# rev_n_v32.net
KiCad netlist of a schematic drawn in EAGLE
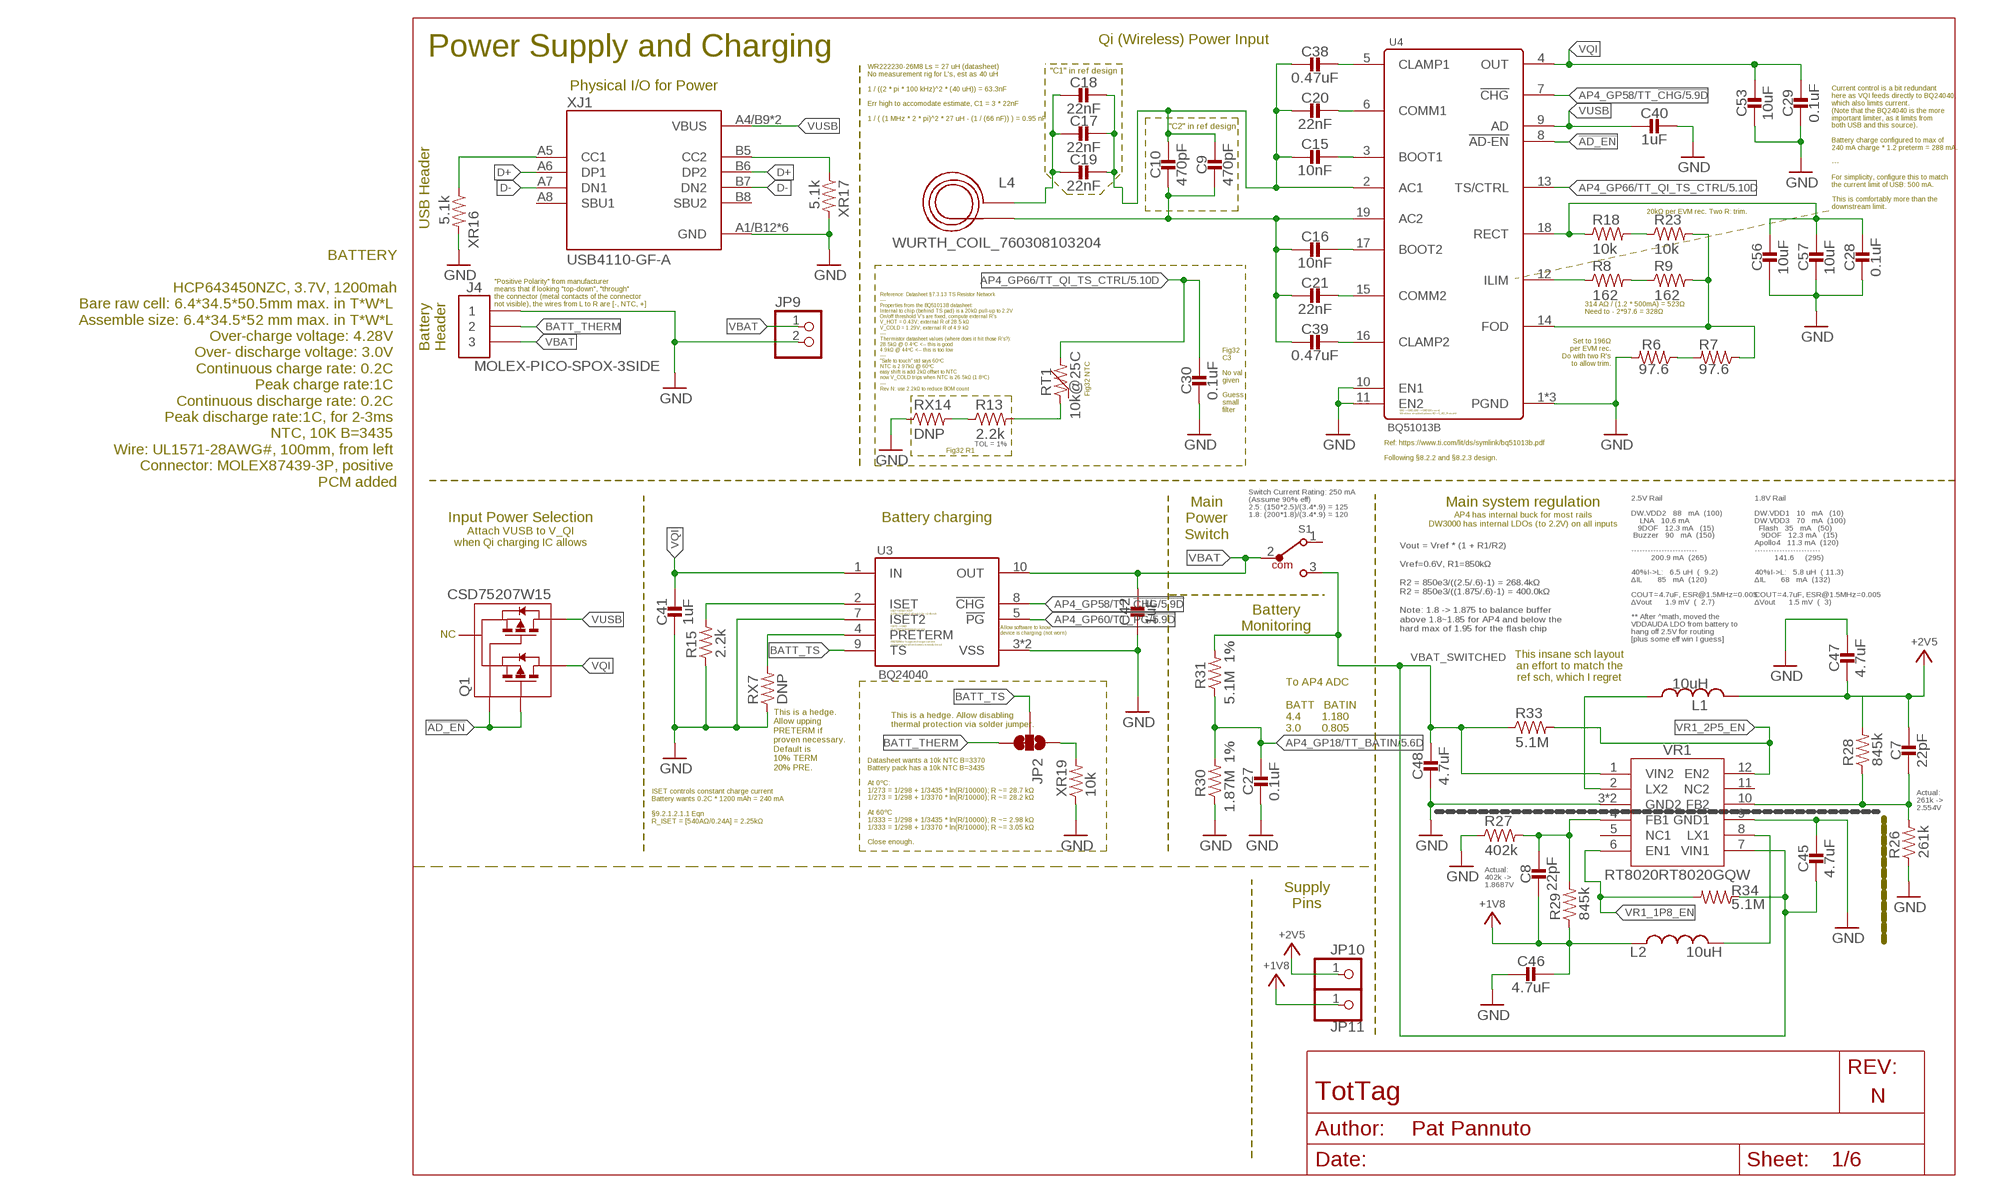
[diagram p0: schematic, sheet 1]
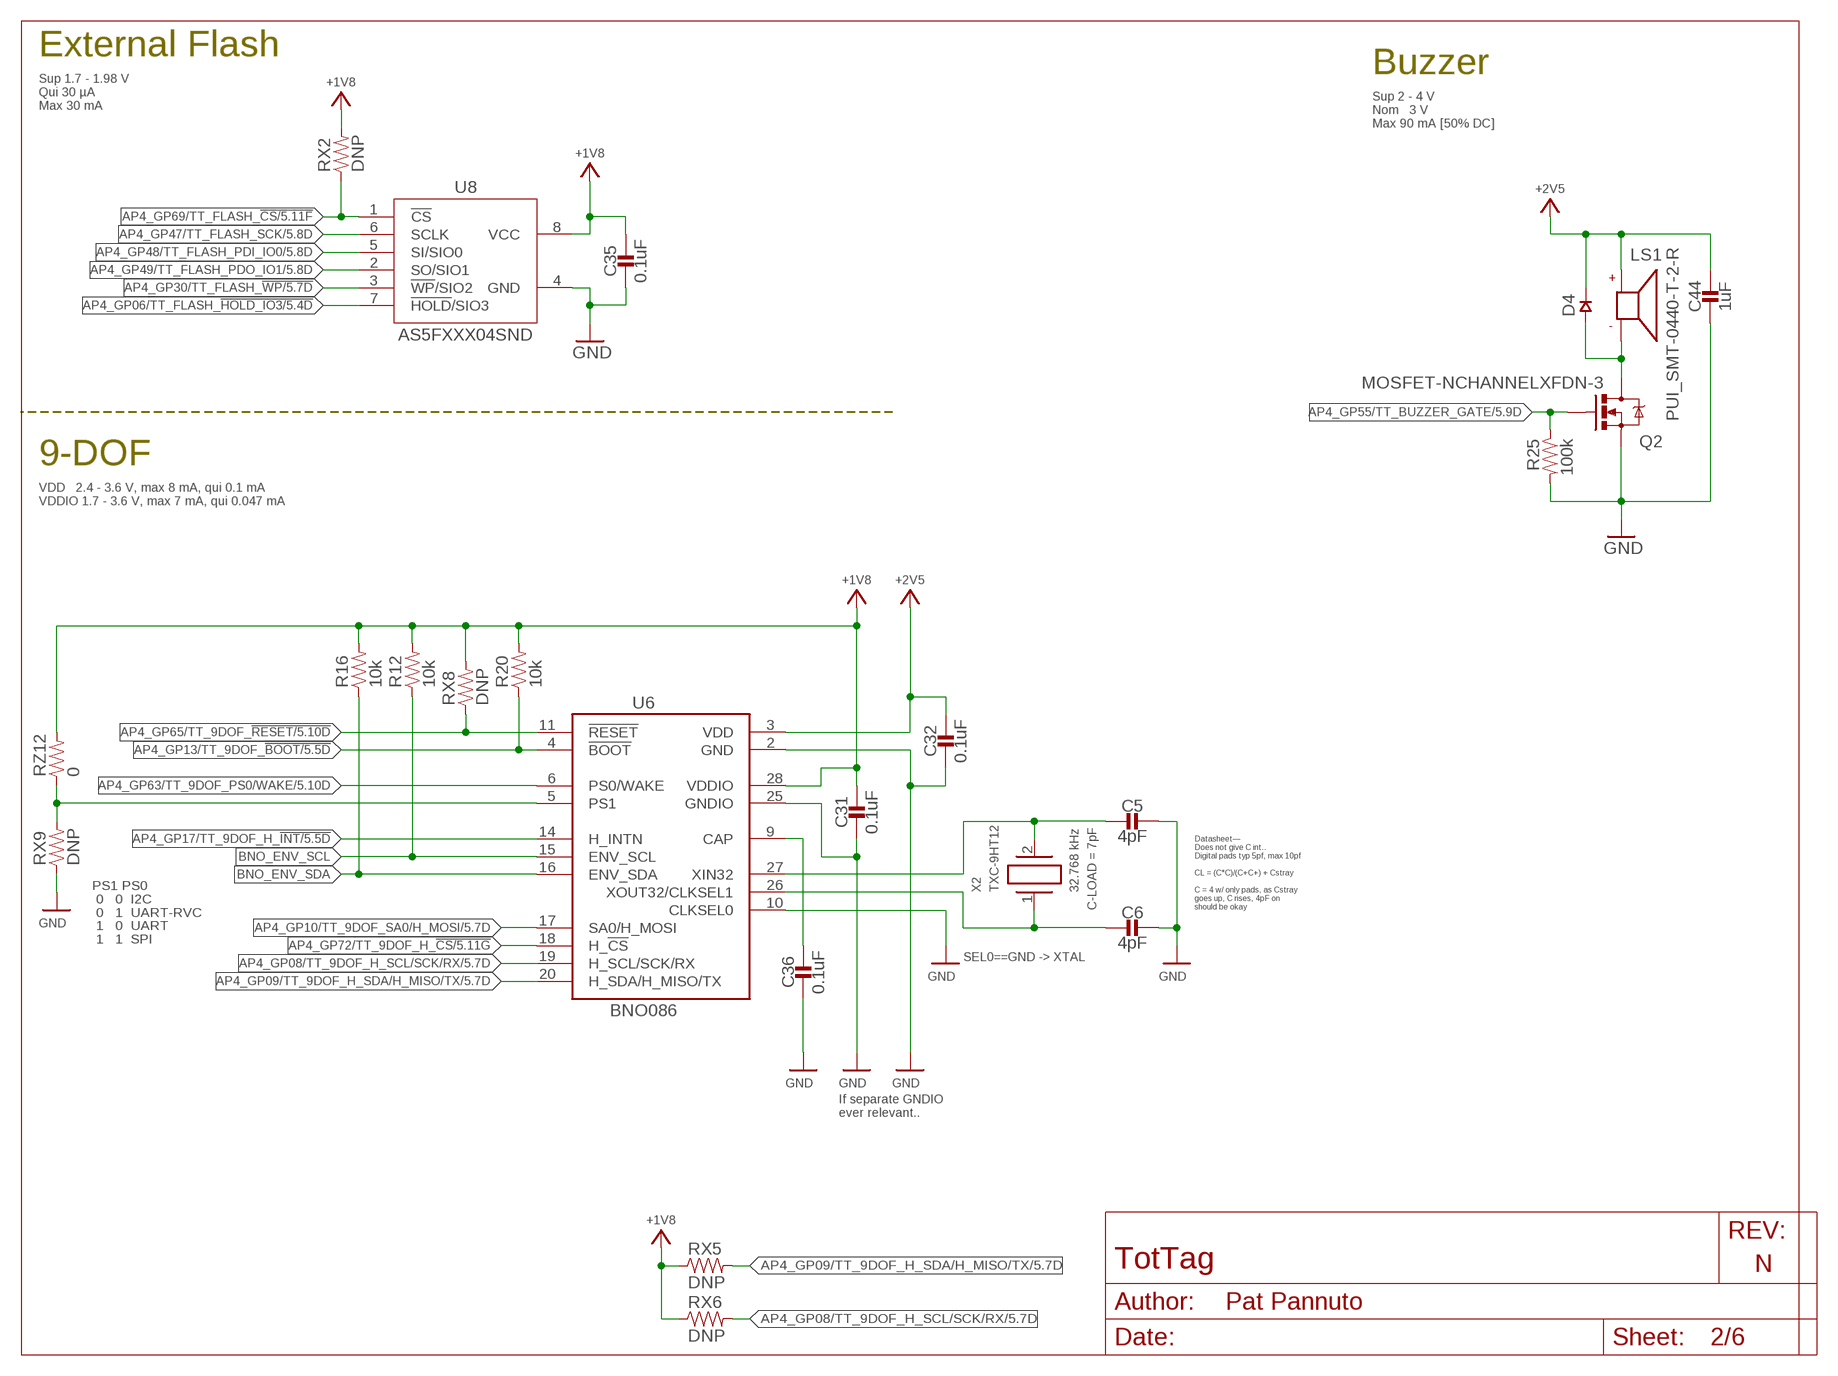
[diagram p1: schematic, sheet 2]
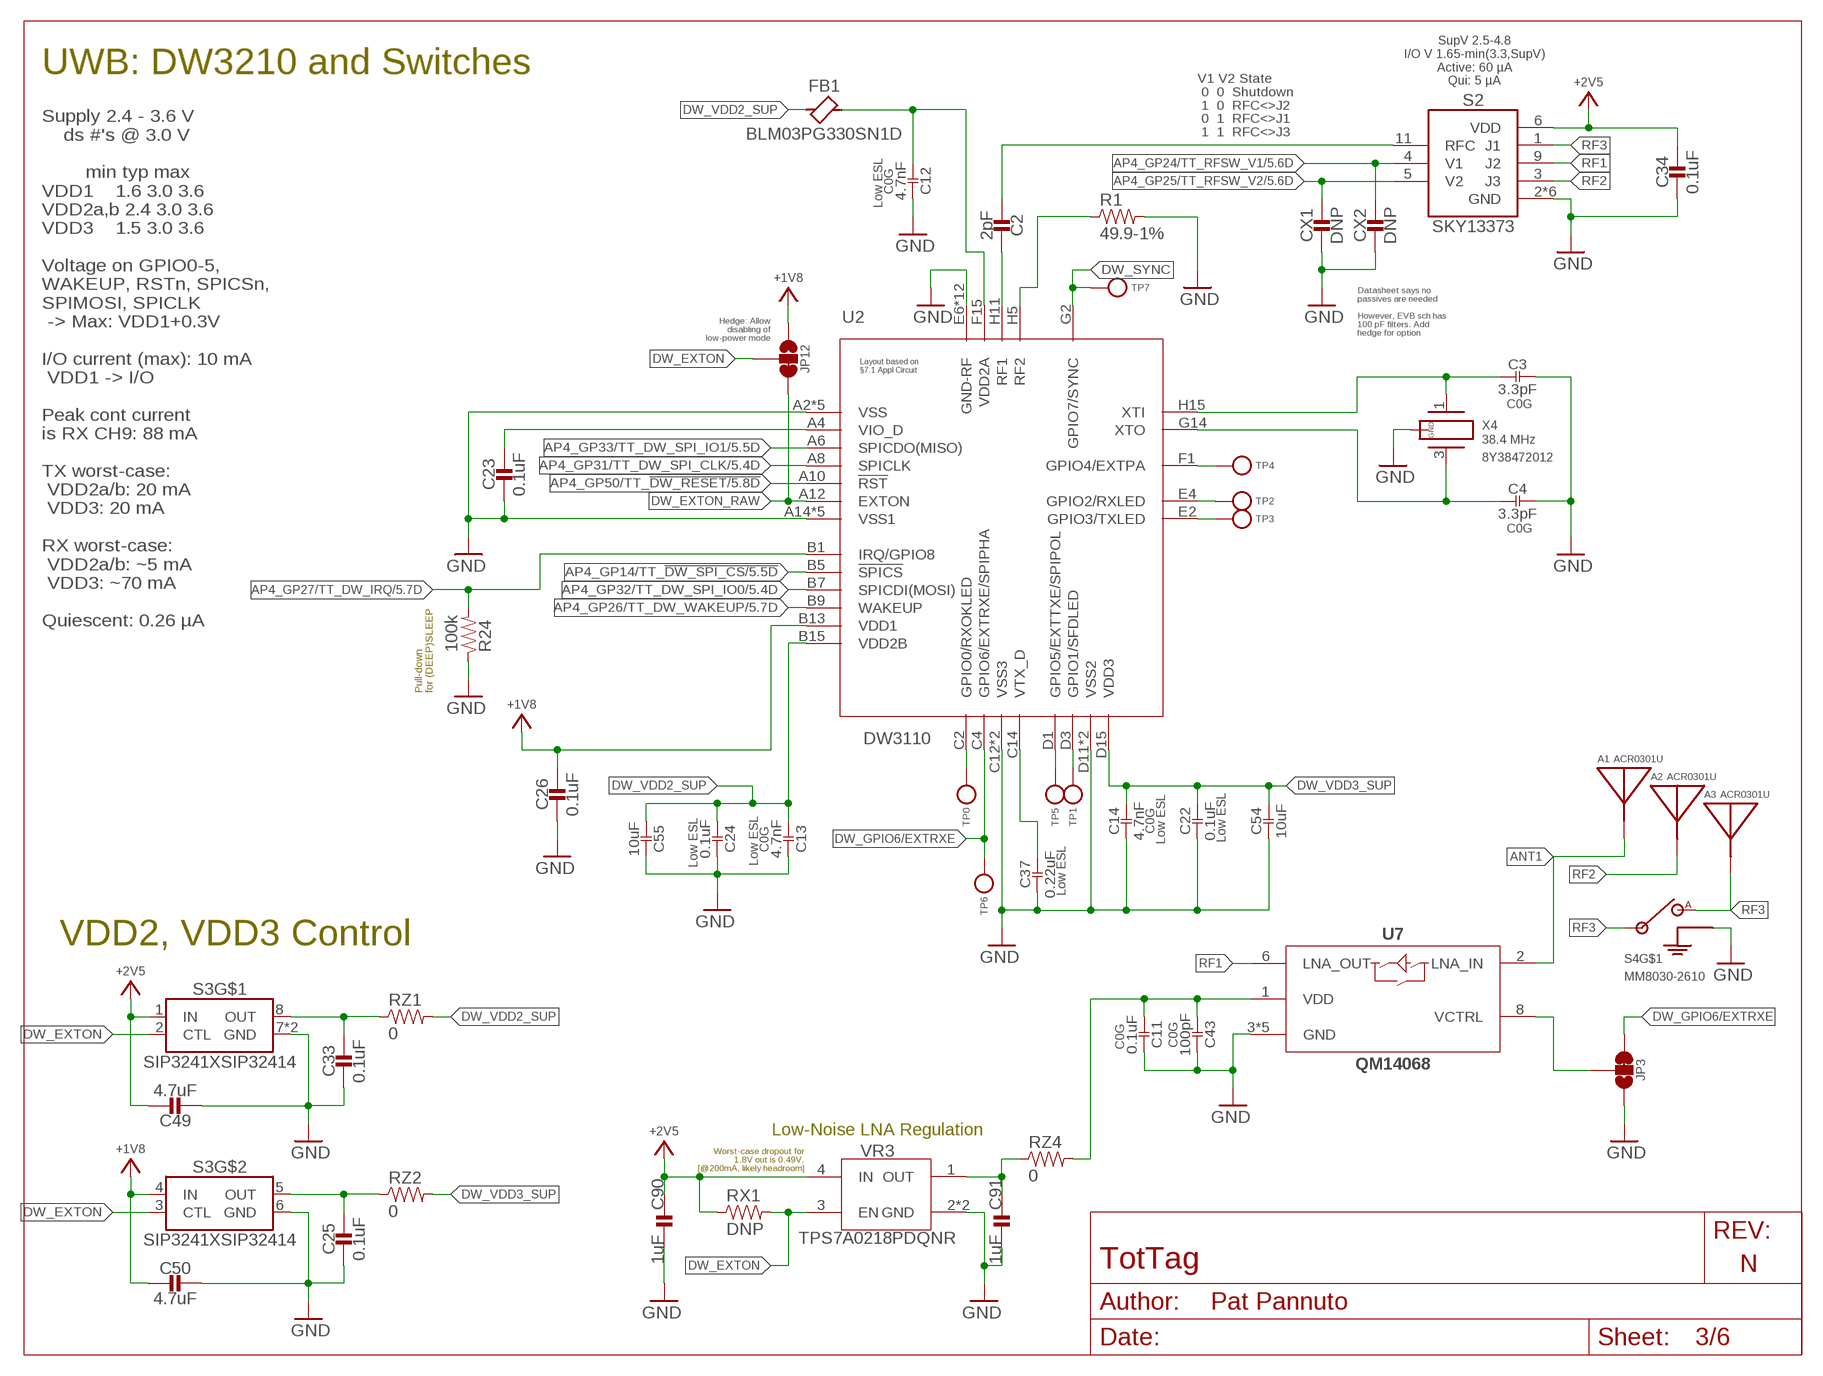
[diagram p2: schematic, sheet 3]
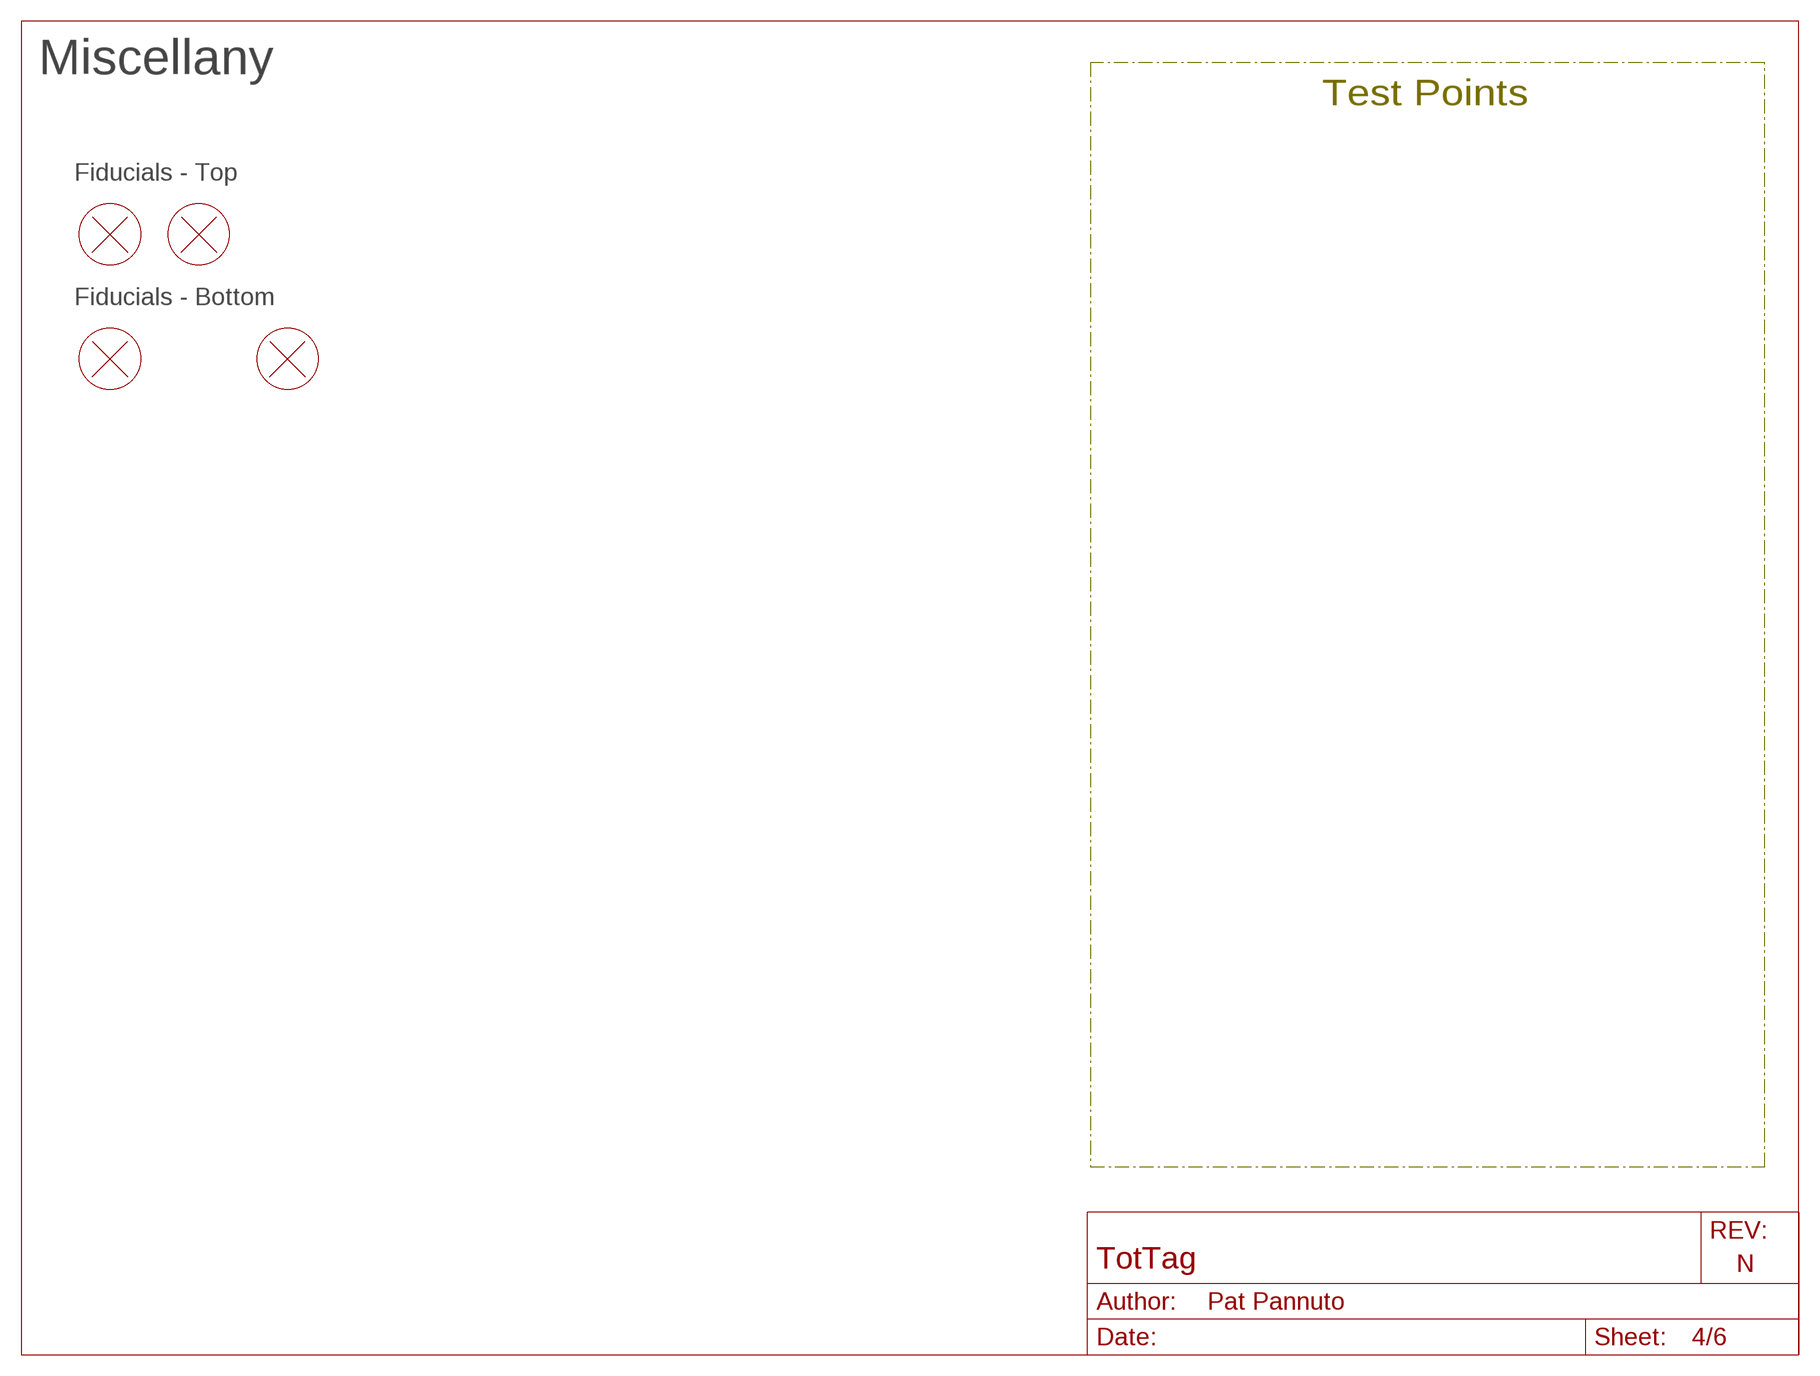
[diagram p3: schematic, sheet 4]
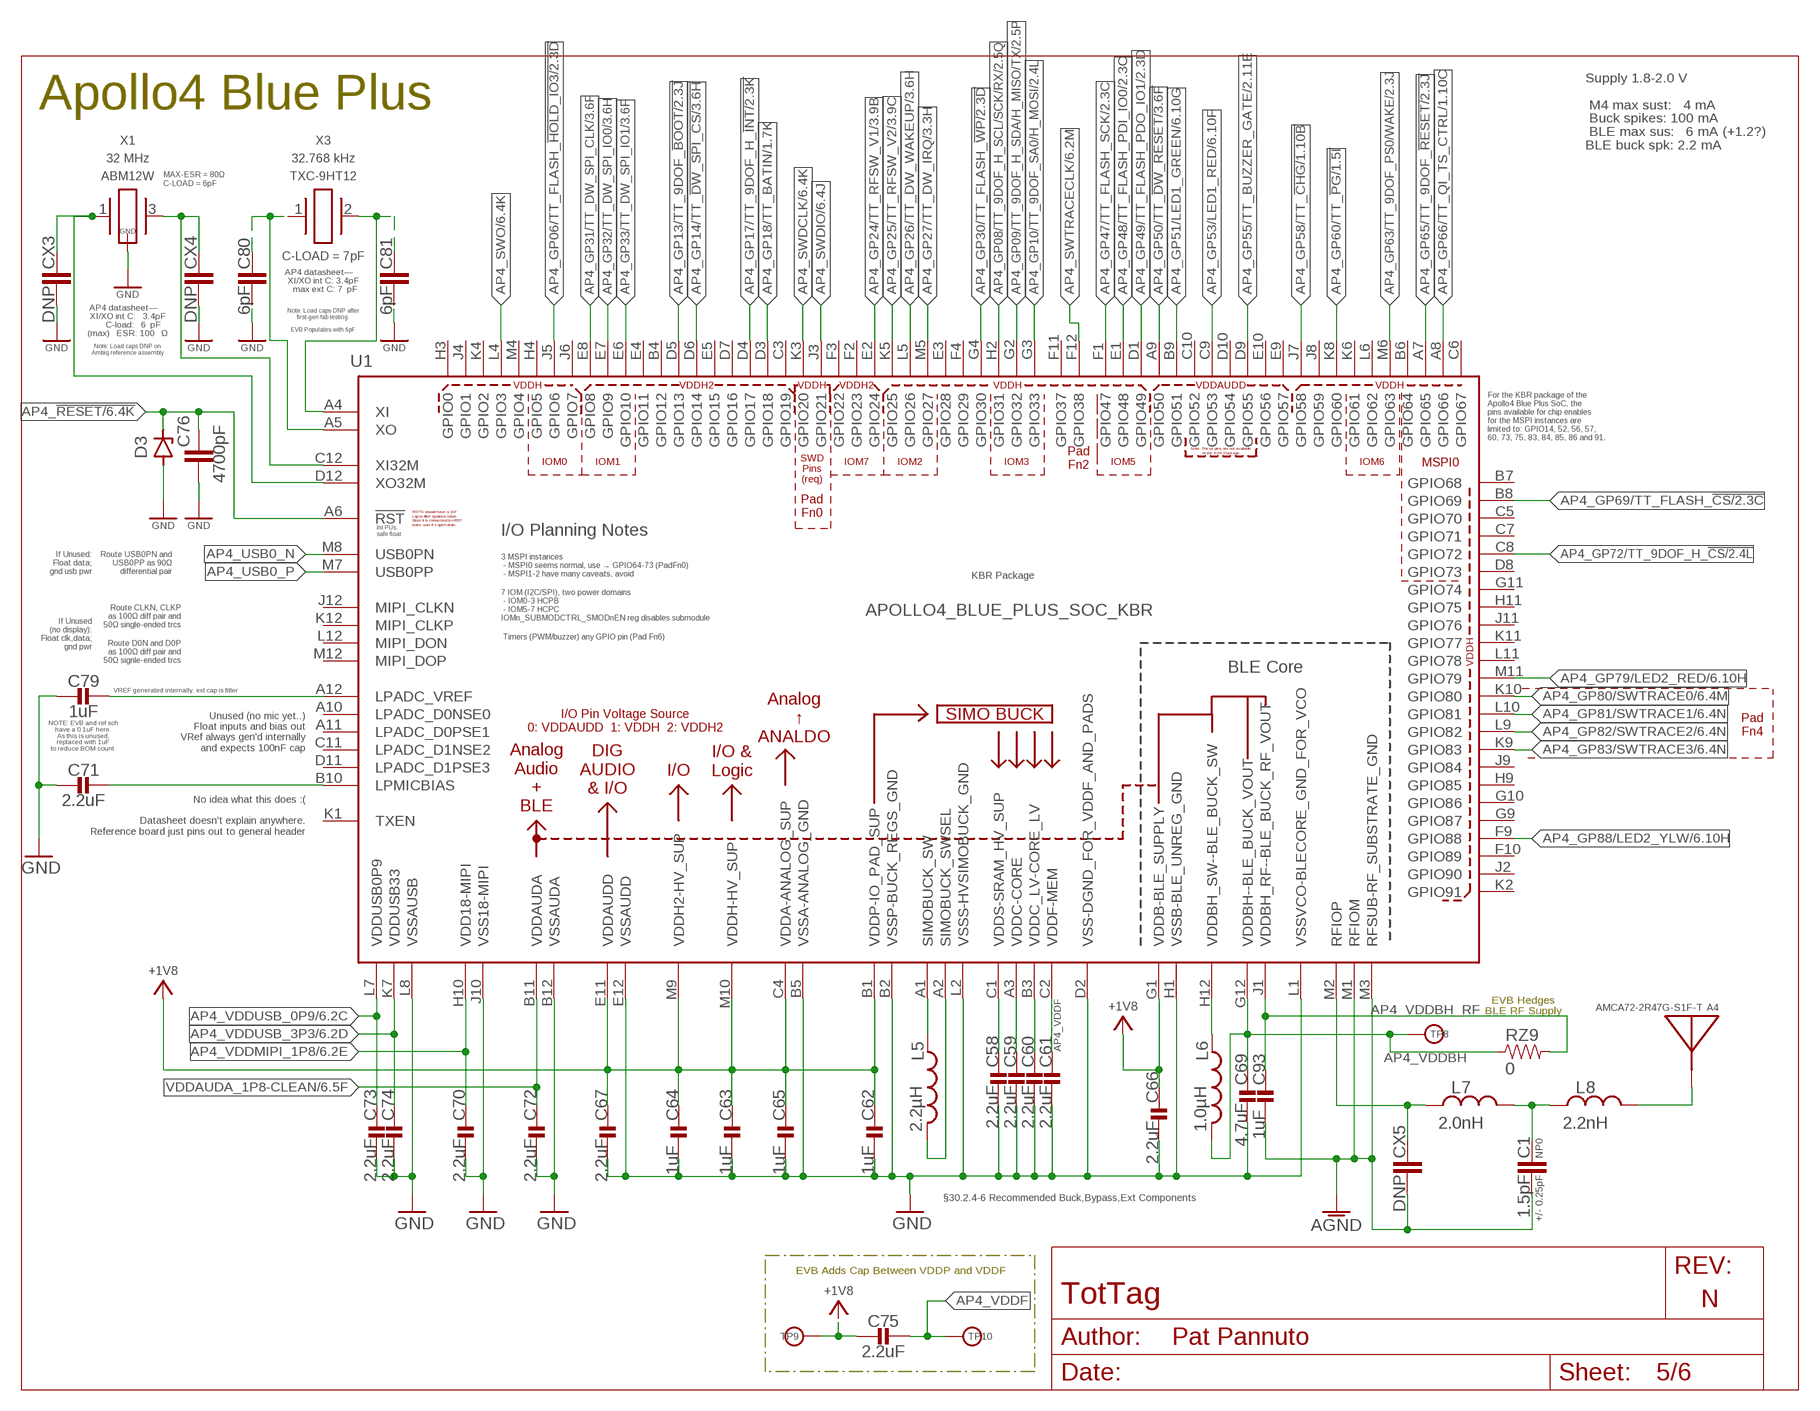
[diagram p4: schematic, sheet 5]
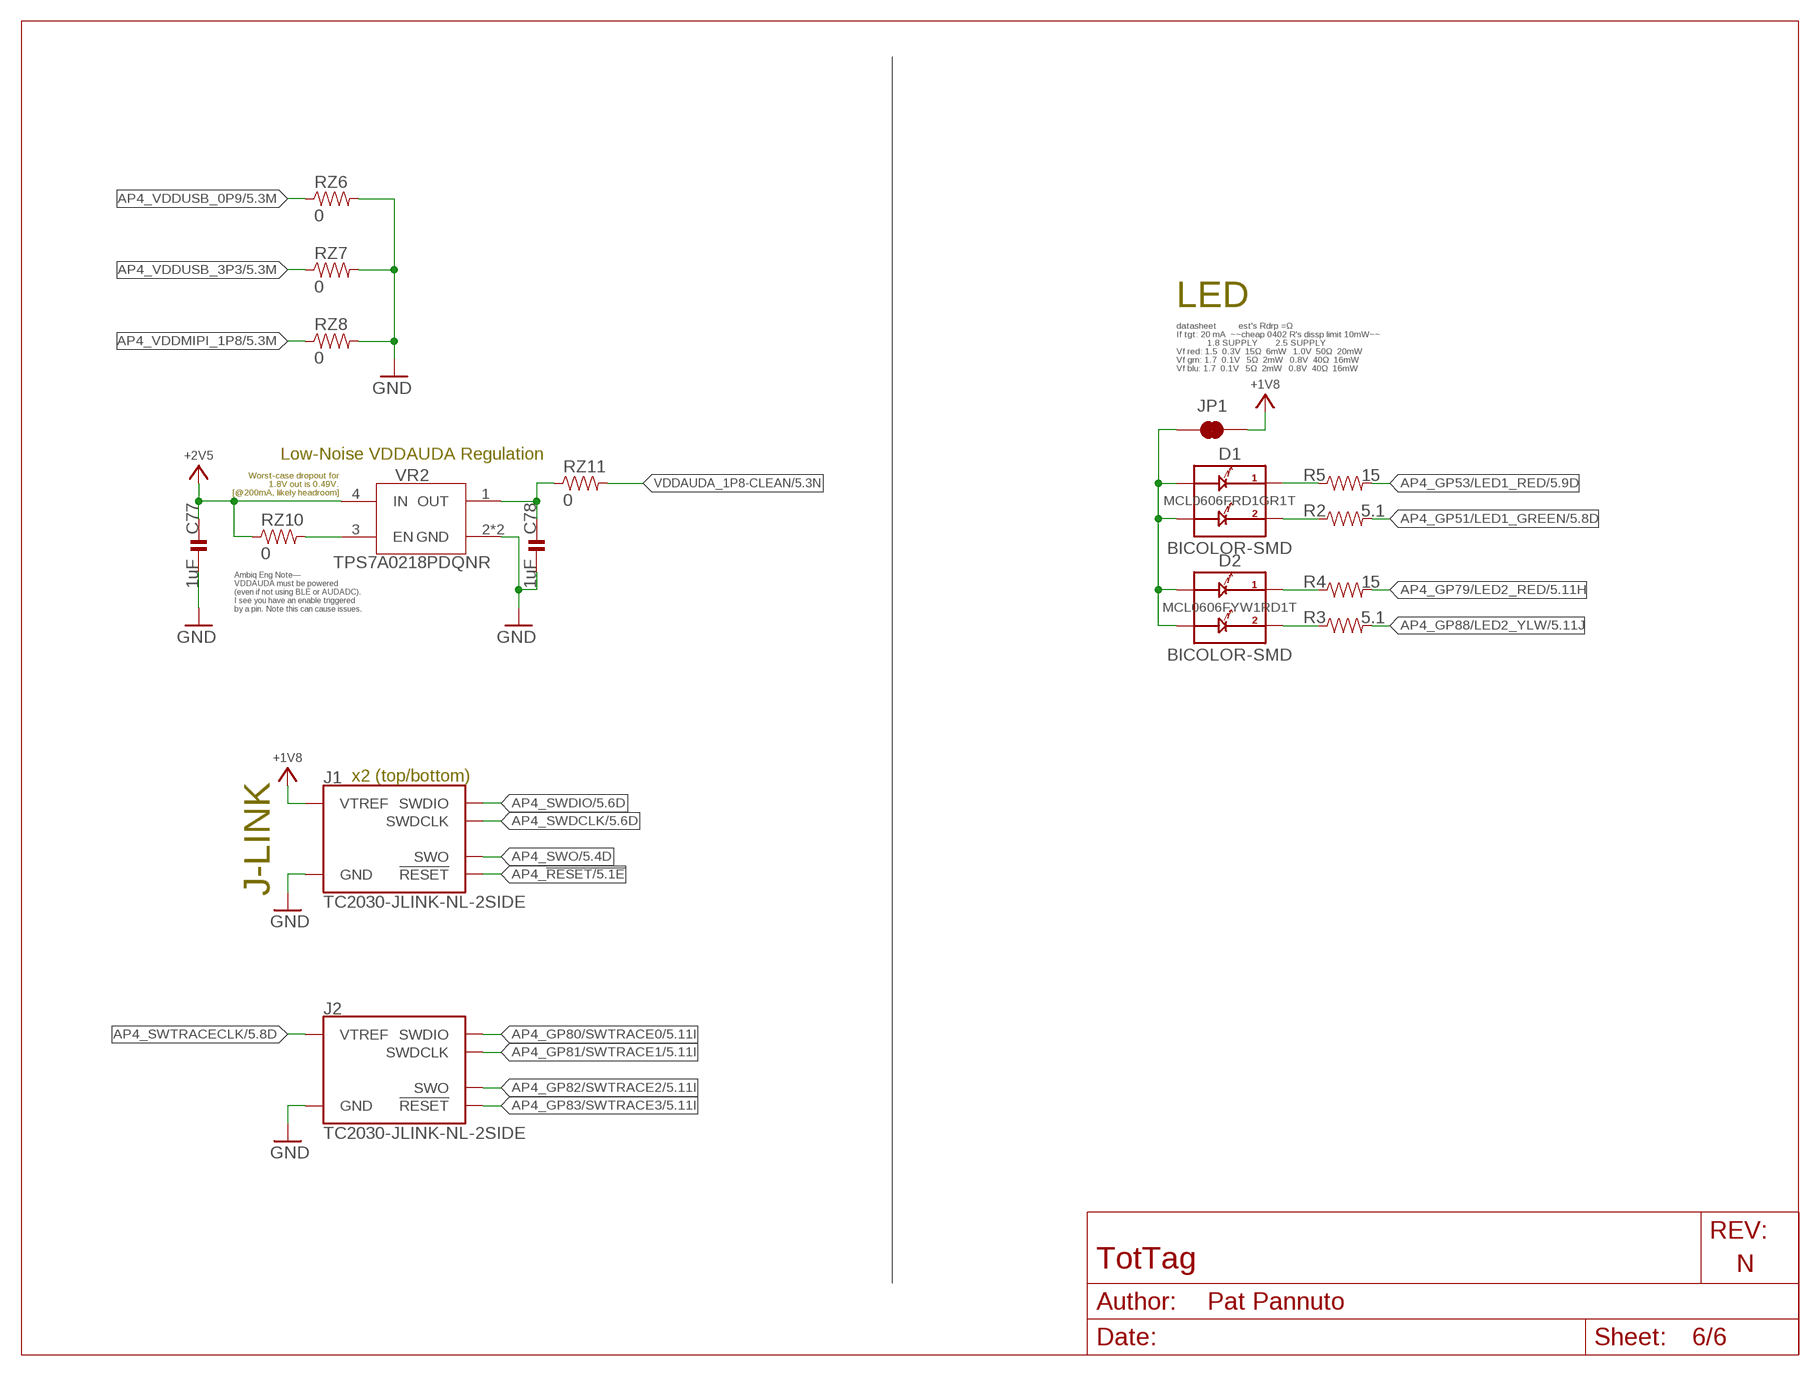
[diagram p5: schematic, sheet 6]

(export (version "E")
  (design (tool "Eeschema 10.0.6"))
  (components
    (comp (ref "C7")
      (value "22pF")
      (footprint "eagle-import:0201_CAP")
      (fields (field (name "MPN") "GRM0335C1H220FA01D"))
      (libsource (lib "eagle-import") (part "passives_20904581_CAPACITOR0201_CAP"))
    )
    (comp (ref "C8")
      (value "22pF")
      (footprint "eagle-import:0201_CAP")
      (fields (field (name "MPN") "GRM0335C1H220FA01D"))
      (libsource (lib "eagle-import") (part "passives_20904581_CAPACITOR0201_CAP"))
    )
    (comp (ref "C9")
      (value "470pF")
      (footprint "eagle-import:0402_CAP")
      (description "CAP CER 470PF 50V C0G/NP0 0402")
      (fields (field (name "MANUFACTURER") "Murata") (field (name "MPN") "GRM1555C1H471JA01J"))
      (libsource (lib "eagle-import") (part "passives_20904581_CAPACITOR0402_CAP"))
    )
    (comp (ref "C10")
      (value "470pF")
      (footprint "eagle-import:0402_CAP")
      (description "CAP CER 470PF 50V C0G/NP0 0402")
      (fields (field (name "MANUFACTURER") "Murata") (field (name "MPN") "GRM1555C1H471JA01J"))
      (libsource (lib "eagle-import") (part "passives_20904581_CAPACITOR0402_CAP"))
    )
    (comp (ref "C15")
      (value "10nF")
      (footprint "eagle-import:0402_CAP")
      (fields (field (name "MPN") "GRM155R71H103KA88J"))
      (libsource (lib "eagle-import") (part "passives_20904581_CAPACITOR0402_CAP"))
    )
    (comp (ref "C16")
      (value "10nF")
      (footprint "eagle-import:0402_CAP")
      (fields (field (name "MPN") "GRM155R71H103KA88J"))
      (libsource (lib "eagle-import") (part "passives_20904581_CAPACITOR0402_CAP"))
    )
    (comp (ref "C17")
      (value "22nF")
      (footprint "eagle-import:0402_CAP")
      (fields (field (name "MPN") "GRM155R71E223JA61D"))
      (libsource (lib "eagle-import") (part "passives_20904581_CAPACITOR0402_CAP"))
    )
    (comp (ref "C18")
      (value "22nF")
      (footprint "eagle-import:0402_CAP")
      (fields (field (name "MPN") "GRM155R71E223JA61D"))
      (libsource (lib "eagle-import") (part "passives_20904581_CAPACITOR0402_CAP"))
    )
    (comp (ref "C19")
      (value "22nF")
      (footprint "eagle-import:0402_CAP")
      (fields (field (name "MPN") "GRM155R71E223JA61D"))
      (libsource (lib "eagle-import") (part "passives_20904581_CAPACITOR0402_CAP"))
    )
    (comp (ref "C20")
      (value "22nF")
      (footprint "eagle-import:0402_CAP")
      (fields (field (name "MPN") "CC0402ZRY5V8BB223"))
      (libsource (lib "eagle-import") (part "passives_20904581_CAPACITOR0402_CAP"))
    )
    (comp (ref "C21")
      (value "22nF")
      (footprint "eagle-import:0402_CAP")
      (fields (field (name "MPN") "CC0402ZRY5V8BB223"))
      (libsource (lib "eagle-import") (part "passives_20904581_CAPACITOR0402_CAP"))
    )
    (comp (ref "C27")
      (value "0.1uF")
      (footprint "eagle-import:0402_CAP")
      (fields (field (name "MPN") "GRM155R71C104KA88J "))
      (libsource (lib "eagle-import") (part "CAPACITOR0402_CAP"))
    )
    (comp (ref "C28")
      (value "0.1uF")
      (footprint "eagle-import:0402_CAP")
      (fields (field (name "MPN") "GRM155R71C104KA88J "))
      (libsource (lib "eagle-import") (part "CAPACITOR0402_CAP"))
    )
    (comp (ref "C29")
      (value "0.1uF")
      (footprint "eagle-import:0402_CAP")
      (fields (field (name "MPN") "GRM155R71C104KA88J "))
      (libsource (lib "eagle-import") (part "CAPACITOR0402_CAP"))
    )
    (comp (ref "C30")
      (value "0.1uF")
      (footprint "eagle-import:0402_CAP")
      (fields (field (name "MPN") "GRM155R71C104KA88J "))
      (libsource (lib "eagle-import") (part "CAPACITOR0402_CAP"))
    )
    (comp (ref "C38")
      (value "0.47uF")
      (footprint "eagle-import:0402_CAP")
      (fields (field (name "MPN") "GRT155R61E474ME01D"))
      (libsource (lib "eagle-import") (part "passives_20904581_CAPACITOR0402_CAP"))
    )
    (comp (ref "C39")
      (value "0.47uF")
      (footprint "eagle-import:0402_CAP")
      (fields (field (name "MPN") "GRT155R61E474ME01D"))
      (libsource (lib "eagle-import") (part "passives_20904581_CAPACITOR0402_CAP"))
    )
    (comp (ref "C40")
      (value "1uF")
      (footprint "eagle-import:0402_CAP")
      (fields (field (name "MPN") "GRM155R70J105KA12J"))
      (libsource (lib "eagle-import") (part "CAPACITOR0402_CAP"))
    )
    (comp (ref "C41")
      (value "1uF")
      (footprint "eagle-import:0402_CAP")
      (fields (field (name "MPN") "GRM155R70J105KA12J"))
      (libsource (lib "eagle-import") (part "CAPACITOR0402_CAP"))
    )
    (comp (ref "C42")
      (value "1uF")
      (footprint "eagle-import:0402_CAP")
      (fields (field (name "MPN") "GRM155R70J105KA12J"))
      (libsource (lib "eagle-import") (part "CAPACITOR0402_CAP"))
    )
    (comp (ref "C45")
      (value "4.7uF")
      (footprint "eagle-import:0603_CAP")
      (fields (field (name "MPN") "C1608X7S1A475K080AC"))
      (libsource (lib "eagle-import") (part "passives_20904581_CAPACITOR0603_CAP"))
    )
    (comp (ref "C46")
      (value "4.7uF")
      (footprint "eagle-import:0603_CAP")
      (fields (field (name "MPN") "C1608X7S1A475K080AC"))
      (libsource (lib "eagle-import") (part "passives_20904581_CAPACITOR0603_CAP"))
    )
    (comp (ref "C47")
      (value "4.7uF")
      (footprint "eagle-import:0603_CAP")
      (fields (field (name "MPN") "C1608X7S1A475K080AC"))
      (libsource (lib "eagle-import") (part "passives_20904581_CAPACITOR0603_CAP"))
    )
    (comp (ref "C48")
      (value "4.7uF")
      (footprint "eagle-import:0603_CAP")
      (fields (field (name "MPN") "C1608X7S1A475K080AC"))
      (libsource (lib "eagle-import") (part "passives_20904581_CAPACITOR0603_CAP"))
    )
    (comp (ref "C53")
      (value "10uF")
      (footprint "eagle-import:0603_CAP")
      (fields (field (name "MPN") "CM105X5R106M25AT"))
      (libsource (lib "eagle-import") (part "passives_20904581_CAPACITOR0603_CAP"))
    )
    (comp (ref "C56")
      (value "10uF")
      (footprint "eagle-import:0603_CAP")
      (fields (field (name "MPN") "CM105X5R106M25AT"))
      (libsource (lib "eagle-import") (part "passives_20904581_CAPACITOR0603_CAP"))
    )
    (comp (ref "C57")
      (value "10uF")
      (footprint "eagle-import:0603_CAP")
      (fields (field (name "MPN") "CM105X5R106M25AT"))
      (libsource (lib "eagle-import") (part "passives_20904581_CAPACITOR0603_CAP"))
    )
    (comp (ref "J4")
      (value "MOLEX-PICO-SPOX-3SIDE")
      (footprint "eagle-import:MOLEX-PICO-SPOX-3_SIDE")
      (libsource (lib "eagle-import") (part "MOLEX-PICO-SPOX-3SIDE"))
    )
    (comp (ref "JP2")
      (value "JUMPER-SMT_3_1-NC_TRACE_SILK")
      (footprint "eagle-import:SMT-JUMPER_3_1-NC_TRACE_SILK")
      (libsource (lib "eagle-import") (part "JUMPER-SMT_3_1-NC_TRACE_SILK"))
    )
    (comp (ref "JP9")
      (value "PINHD-1X2")
      (footprint "eagle-import:1X02")
      (libsource (lib "eagle-import") (part "PINHD-1X2"))
    )
    (comp (ref "JP10")
      (value "PINHD-1X1")
      (footprint "eagle-import:1X01")
      (libsource (lib "eagle-import") (part "PINHD-1X1"))
    )
    (comp (ref "JP11")
      (value "PINHD-1X1")
      (footprint "eagle-import:1X01")
      (libsource (lib "eagle-import") (part "PINHD-1X1"))
    )
    (comp (ref "L1")
      (value "10uH")
      (footprint "eagle-import:NRX3015")
      (fields (field (name "MANUFACTURER") "TAIYO YUDEN") (field (name "MPN") "NR3015T100M"))
      (libsource (lib "eagle-import") (part "INDUCTORNRX3015"))
    )
    (comp (ref "L2")
      (value "10uH")
      (footprint "eagle-import:NRX3015")
      (fields (field (name "MANUFACTURER") "TAIYO YUDEN") (field (name "MPN") "NR3015T100M"))
      (libsource (lib "eagle-import") (part "INDUCTORNRX3015"))
    )
    (comp (ref "L4")
      (value "WURTH_COIL_760308103204")
      (footprint "eagle-import:WURTH_COIL_760308103204")
      (fields (field (name "MANUFACTURER") "Würth Elektronik") (field (name "MPN") "760308103204"))
      (libsource (lib "eagle-import") (part "WURTH_COIL_760308103204"))
    )
    (comp (ref "Q1")
      (value "CSD75207W15")
      (footprint "eagle-import:DSBGA")
      (fields (field (name "MANUFACTURER") "TEXAS INSTRUMENTS"))
      (libsource (lib "eagle-import") (part "CSD75207W15"))
    )
    (comp (ref "R6")
      (value "97.6")
      (footprint "eagle-import:0402_RES")
      (fields (field (name "MPN") "RMCF0402FT97R6"))
      (libsource (lib "eagle-import") (part "passives_20904581_RESISTOR0402_RES"))
    )
    (comp (ref "R7")
      (value "97.6")
      (footprint "eagle-import:0402_RES")
      (fields (field (name "MPN") "RMCF0402FT97R6"))
      (libsource (lib "eagle-import") (part "passives_20904581_RESISTOR0402_RES"))
    )
    (comp (ref "R8")
      (value "162")
      (footprint "eagle-import:0402_RES")
      (fields (field (name "MPN") "RMCF0402FT162R"))
      (libsource (lib "eagle-import") (part "passives_20904581_RESISTOR0402_RES"))
    )
    (comp (ref "R9")
      (value "162")
      (footprint "eagle-import:0402_RES")
      (fields (field (name "MPN") "RMCF0402FT162R"))
      (libsource (lib "eagle-import") (part "passives_20904581_RESISTOR0402_RES"))
    )
    (comp (ref "R13")
      (value "2.2k")
      (footprint "eagle-import:0402_RES")
      (fields (field (name "MPN") "RC0402FR-072K2L") (field (name "TOL") "1%"))
      (libsource (lib "eagle-import") (part "RESISTOR0402_RES"))
    )
    (comp (ref "R15")
      (value "2.2k")
      (footprint "eagle-import:0402_RES")
      (fields (field (name "MPN") "RC0402FR-072K2L"))
      (libsource (lib "eagle-import") (part "passives_20904581_RESISTOR0402_RES"))
    )
    (comp (ref "R18")
      (value "10k")
      (footprint "eagle-import:0402_RES")
      (fields (field (name "MPN") "RC0402JR-0710KL"))
      (libsource (lib "eagle-import") (part "RESISTOR0402_RES"))
    )
    (comp (ref "R23")
      (value "10k")
      (footprint "eagle-import:0402_RES")
      (fields (field (name "MPN") "RC0402JR-0710KL"))
      (libsource (lib "eagle-import") (part "RESISTOR0402_RES"))
    )
    (comp (ref "R26")
      (value "261k")
      (footprint "eagle-import:0201_RES")
      (fields (field (name "MPN") "ERJ-1GNF2613C"))
      (libsource (lib "eagle-import") (part "passives_20904581_RESISTOR0201_RES"))
    )
    (comp (ref "R27")
      (value "402k")
      (footprint "eagle-import:0201_RES")
      (fields (field (name "MPN") "ERJ-1GNF4023C"))
      (libsource (lib "eagle-import") (part "passives_20904581_RESISTOR0201_RES"))
    )
    (comp (ref "R28")
      (value "845k")
      (footprint "eagle-import:0201_RES")
      (fields (field (name "MPN") "ERJ-1GNF8453C"))
      (libsource (lib "eagle-import") (part "passives_20904581_RESISTOR0201_RES"))
    )
    (comp (ref "R29")
      (value "845k")
      (footprint "eagle-import:0201_RES")
      (fields (field (name "MPN") "ERJ-1GNF8453C"))
      (libsource (lib "eagle-import") (part "passives_20904581_RESISTOR0201_RES"))
    )
    (comp (ref "R30")
      (value "1.87M")
      (footprint "eagle-import:0402_RES")
      (fields (field (name "MPN") "RMCF0402FT1M87") (field (name "TOLERANCE") "1%"))
      (libsource (lib "eagle-import") (part "RESISTOR0402_RES"))
    )
    (comp (ref "R31")
      (value "5.1M")
      (footprint "eagle-import:0402_RES")
      (fields (field (name "MPN") "RMCF0402FT5M10") (field (name "TOLERANCE") "1%"))
      (libsource (lib "eagle-import") (part "RESISTOR0402_RES"))
    )
    (comp (ref "R33")
      (value "5.1M")
      (footprint "eagle-import:0402_RES")
      (fields (field (name "MPN") "RMCF0402FT5M10"))
      (libsource (lib "eagle-import") (part "RESISTOR0402_RES"))
    )
    (comp (ref "R34")
      (value "5.1M")
      (footprint "eagle-import:0402_RES")
      (fields (field (name "MPN") "RMCF0402FT5M10"))
      (libsource (lib "eagle-import") (part "RESISTOR0402_RES"))
    )
    (comp (ref "RT1")
      (value "10k@25C")
      (footprint "eagle-import:0402_RES")
      (fields (field (name "MPN") "NCU15XH103F60RC"))
      (libsource (lib "eagle-import") (part "THERMISTOR0402"))
    )
    (comp (ref "RX7")
      (value "DNP")
      (footprint "eagle-import:0402_RES")
      (libsource (lib "eagle-import") (part "passives_20904581_RESISTOR0402_RES"))
    )
    (comp (ref "RX14")
      (value "DNP")
      (footprint "eagle-import:0402_RES")
      (libsource (lib "eagle-import") (part "RESISTOR0402_RES"))
    )
    (comp (ref "S1")
      (value "450404015514")
      (footprint "eagle-import:450404015514")
      (libsource (lib "eagle-import") (part "450404015514"))
    )
    (comp (ref "U3")
      (value "BQ24040")
      (footprint "eagle-import:DSQ0010A")
      (fields (field (name "MPN") "BQ24040DSQR"))
      (libsource (lib "eagle-import") (part "BQ24040"))
    )
    (comp (ref "U4")
      (value "BQ51013B")
      (footprint "eagle-import:RHL0020A")
      (fields (field (name "MPN") "BQ51013BRHLR"))
      (libsource (lib "eagle-import") (part "BQ51013B"))
    )
    (comp (ref "VR1")
      (value "RT8020RT8020GQW")
      (footprint "eagle-import:SON45P300X300X80-13T160X250N")
      (fields (field (name "MANUFACTURER") "RichTek") (field (name "MPN") "RT8020GQW"))
      (libsource (lib "eagle-import") (part "RT8020RT8020GQW"))
    )
    (comp (ref "XJ1")
      (value "USB4110-GF-A")
      (footprint "eagle-import:GCT_USB4110-GF-A")
      (fields (field (name "MF") "GCT"))
      (libsource (lib "eagle-import") (part "USB4110-GF-A"))
    )
    (comp (ref "XR16")
      (value "5.1k")
      (footprint "eagle-import:0402_RES")
      (fields (field (name "MPN") "RMCF0402FT5K10"))
      (libsource (lib "eagle-import") (part "passives_20904581_RESISTOR0402_RES"))
    )
    (comp (ref "XR17")
      (value "5.1k")
      (footprint "eagle-import:0402_RES")
      (fields (field (name "MPN") "RMCF0402FT5K10"))
      (libsource (lib "eagle-import") (part "passives_20904581_RESISTOR0402_RES"))
    )
    (comp (ref "XR19")
      (value "10k")
      (footprint "eagle-import:0402_RES")
      (fields (field (name "MPN") "RC0402JR-0710KL"))
      (libsource (lib "eagle-import") (part "RESISTOR0402_RES"))
    )
    (comp (ref "C77")
      (value "1uF")
      (footprint "eagle-import:0201_CAP")
      (fields (field (name "MANUFACTURER") "Murata") (field (name "MPN") "GRM033R61A105ME44D"))
      (libsource (lib "eagle-import") (part "passives_20904581_CAPACITOR0201_CAP"))
    )
    (comp (ref "C78")
      (value "1uF")
      (footprint "eagle-import:0201_CAP")
      (fields (field (name "MANUFACTURER") "Murata") (field (name "MPN") "GRM033R61A105ME44D"))
      (libsource (lib "eagle-import") (part "passives_20904581_CAPACITOR0201_CAP"))
    )
    (comp (ref "D1")
      (value "BICOLOR-SMD")
      (footprint "eagle-import:LED-0606")
      (fields (field (name "MPN") "MCL0606FRD1GR1T"))
      (libsource (lib "eagle-import") (part "BICOLOR-SMD"))
    )
    (comp (ref "D2")
      (value "BICOLOR-SMD")
      (footprint "eagle-import:LED-0606")
      (fields (field (name "MPN") "MCL0606FYW1RD1T"))
      (libsource (lib "eagle-import") (part "BICOLOR-SMD"))
    )
    (comp (ref "J1")
      (value "TC2030-JLINK-NL-2SIDE")
      (footprint "eagle-import:TC2030-IDC-NL-2SIDE")
      (libsource (lib "eagle-import") (part "TC2030-JLINK-NL-2SIDE"))
    )
    (comp (ref "J2")
      (value "TC2030-JLINK-NL-2SIDE")
      (footprint "eagle-import:TC2030-IDC-NL-2SIDE")
      (libsource (lib "eagle-import") (part "TC2030-JLINK-NL-2SIDE"))
    )
    (comp (ref "JP1")
      (value "JUMPER-SMT_2_NC_TRACE_SILK")
      (footprint "eagle-import:SMT-JUMPER_2_NC_TRACE_SILK")
      (libsource (lib "eagle-import") (part "JUMPER-SMT_2_NC_TRACE_SILK"))
    )
    (comp (ref "R2")
      (value "5.1")
      (footprint "eagle-import:0402_RES")
      (fields (field (name "MPN") "RC0402JR-075R1L"))
      (libsource (lib "eagle-import") (part "RESISTOR0402_RES"))
    )
    (comp (ref "R3")
      (value "5.1")
      (footprint "eagle-import:0402_RES")
      (fields (field (name "MPN") "RC0402JR-075R1L"))
      (libsource (lib "eagle-import") (part "RESISTOR0402_RES"))
    )
    (comp (ref "R4")
      (value "15")
      (footprint "eagle-import:0402_RES")
      (fields (field (name "MPN") "RC0402JR-0715RL"))
      (libsource (lib "eagle-import") (part "RESISTOR0402_RES"))
    )
    (comp (ref "R5")
      (value "15")
      (footprint "eagle-import:0402_RES")
      (fields (field (name "MPN") "RC0402JR-0715RL"))
      (libsource (lib "eagle-import") (part "RESISTOR0402_RES"))
    )
    (comp (ref "RZ6")
      (value "0")
      (footprint "eagle-import:0402_RES")
      (fields (field (name "MPN") "RMCF0402ZT0R00"))
      (libsource (lib "eagle-import") (part "passives_20904581_RESISTOR0402_RES"))
    )
    (comp (ref "RZ7")
      (value "0")
      (footprint "eagle-import:0402_RES")
      (fields (field (name "MPN") "RMCF0402ZT0R00"))
      (libsource (lib "eagle-import") (part "passives_20904581_RESISTOR0402_RES"))
    )
    (comp (ref "RZ8")
      (value "0")
      (footprint "eagle-import:0402_RES")
      (fields (field (name "MPN") "RMCF0402ZT0R00"))
      (libsource (lib "eagle-import") (part "passives_20904581_RESISTOR0402_RES"))
    )
    (comp (ref "RZ10")
      (value "0")
      (footprint "eagle-import:0402_RES")
      (fields (field (name "MPN") "RMCF0402ZT0R00"))
      (libsource (lib "eagle-import") (part "passives_20904581_RESISTOR0402_RES"))
    )
    (comp (ref "RZ11")
      (value "0")
      (footprint "eagle-import:0402_RES")
      (fields (field (name "MPN") "RMCF0402ZT0R00"))
      (libsource (lib "eagle-import") (part "passives_20904581_RESISTOR0402_RES"))
    )
    (comp (ref "VR2")
      (value "TPS7A0218PDQNR")
      (footprint "eagle-import:4-XDFN-EP")
      (libsource (lib "eagle-import") (part "TPS7A0218PDQNR"))
    )
    (comp (ref "A1")
      (value "ACR0301U")
      (footprint "eagle-import:ACR0301U")
      (fields (field (name "MANUFACTURER") "Abracon"))
      (libsource (lib "eagle-import") (part "ACR0301U"))
    )
    (comp (ref "A2")
      (value "ACR0301U")
      (footprint "eagle-import:ACR0301U")
      (fields (field (name "MANUFACTURER") "Abracon"))
      (libsource (lib "eagle-import") (part "ACR0301U"))
    )
    (comp (ref "A3")
      (value "ACR0301U")
      (footprint "eagle-import:ACR0301U")
      (fields (field (name "MANUFACTURER") "Abracon"))
      (libsource (lib "eagle-import") (part "ACR0301U"))
    )
    (comp (ref "C2")
      (value "2pF")
      (footprint "eagle-import:0201_CAP")
      (fields (field (name "MPN") "CBR02C209A5GAC"))
      (libsource (lib "eagle-import") (part "CAPACITOR0201_CAP"))
    )
    (comp (ref "C3")
      (value "3.3pF")
      (footprint "eagle-import:SMD_2012M-0805US-C")
      (fields
        (field (name "EIA") "C0G")
        (field (name "MANUFACTURER") "KYOCERA AVX")
        (field (name "MPN") "600F3R3BT250XT")
      )
      (libsource (lib "eagle-import") (part "C0805US"))
    )
    (comp (ref "C4")
      (value "3.3pF")
      (footprint "eagle-import:SMD_2012M-0805US-C")
      (fields
        (field (name "EIA") "C0G")
        (field (name "MANUFACTURER") "KYOCERA AVX")
        (field (name "MPN") "600F3R3BT250XT")
      )
      (libsource (lib "eagle-import") (part "C0805US"))
    )
    (comp (ref "C11")
      (value "0.1uF")
      (footprint "eagle-import:SMD_3216M-1206US-C")
      (fields (field (name "EIA") "C0G") (field (name "MPN") "GRM31C5C1H104JA01L"))
      (libsource (lib "eagle-import") (part "C1206US"))
    )
    (comp (ref "C12")
      (value "4.7nF")
      (footprint "eagle-import:SMD_1608M-0603US-C")
      (fields
        (field (name "EIA") "C0G")
        (field (name "FEATURES") "Low ESL")
        (field (name "MANUFACTURER") "KEMET")
        (field (name "MPN") "C0603C472J5GAC7867")
      )
      (libsource (lib "eagle-import") (part "C0603US"))
    )
    (comp (ref "C13")
      (value "4.7nF")
      (footprint "eagle-import:SMD_1608M-0603US-C")
      (fields
        (field (name "EIA") "C0G")
        (field (name "FEATURES") "Low ESL")
        (field (name "MANUFACTURER") "KEMET")
        (field (name "MPN") "C0603C472J5GAC7867")
      )
      (libsource (lib "eagle-import") (part "C0603US"))
    )
    (comp (ref "C14")
      (value "4.7nF")
      (footprint "eagle-import:SMD_1608M-0603US-C")
      (fields
        (field (name "EIA") "C0G")
        (field (name "FEATURES") "Low ESL")
        (field (name "MANUFACTURER") "KEMET")
        (field (name "MPN") "C0603C472J5GAC7867")
      )
      (libsource (lib "eagle-import") (part "C0603US"))
    )
    (comp (ref "C22")
      (value "0.1uF")
      (footprint "eagle-import:SMD_1608M-0603US-C")
      (fields (field (name "FEATURES") "Low ESL") (field (name "MPN") "C1608X7R1H104K080AA"))
      (libsource (lib "eagle-import") (part "C0603US"))
    )
    (comp (ref "C23")
      (value "0.1uF")
      (footprint "eagle-import:0402_CAP")
      (fields (field (name "MPN") "CL05A104KP5NNNC"))
      (libsource (lib "eagle-import") (part "passives_20904581_CAPACITOR0402_CAP"))
    )
    (comp (ref "C24")
      (value "0.1uF")
      (footprint "eagle-import:SMD_1608M-0603US-C")
      (fields (field (name "FEATURES") "Low ESL") (field (name "MPN") "C1608X7R1H104K080AA"))
      (libsource (lib "eagle-import") (part "C0603US"))
    )
    (comp (ref "C25")
      (value "0.1uF")
      (footprint "eagle-import:0402_CAP")
      (fields (field (name "MPN") "CL05A104KP5NNNC"))
      (libsource (lib "eagle-import") (part "passives_20904581_CAPACITOR0402_CAP"))
    )
    (comp (ref "C26")
      (value "0.1uF")
      (footprint "eagle-import:0402_CAP")
      (fields (field (name "MPN") "CL05A104KP5NNNC"))
      (libsource (lib "eagle-import") (part "passives_20904581_CAPACITOR0402_CAP"))
    )
    (comp (ref "C33")
      (value "0.1uF")
      (footprint "eagle-import:0402_CAP")
      (fields (field (name "MPN") "CL05A104KP5NNNC"))
      (libsource (lib "eagle-import") (part "passives_20904581_CAPACITOR0402_CAP"))
    )
    (comp (ref "C34")
      (value "0.1uF")
      (footprint "eagle-import:0402_CAP")
      (fields (field (name "MPN") "CL05A104KP5NNNC"))
      (libsource (lib "eagle-import") (part "passives_20904581_CAPACITOR0402_CAP"))
    )
    (comp (ref "C37")
      (value "0.22uF")
      (footprint "eagle-import:SMD_1608M-0603US-C")
      (fields (field (name "FEATURES") "Low ESL") (field (name "MPN") "C1608X7R1H224K080AB"))
      (libsource (lib "eagle-import") (part "C0603US"))
    )
    (comp (ref "C43")
      (value "100pF")
      (footprint "eagle-import:SMD_1005M-0402US-C")
      (fields (field (name "EIA") "C0G") (field (name "MPN") "C0402C101J3GACTU"))
      (libsource (lib "eagle-import") (part "C0402US"))
    )
    (comp (ref "C49")
      (value "4.7uF")
      (footprint "eagle-import:0603_CAP")
      (fields (field (name "MPN") "C1608X7S1A475K080AC"))
      (libsource (lib "eagle-import") (part "passives_20904581_CAPACITOR0603_CAP"))
    )
    (comp (ref "C50")
      (value "4.7uF")
      (footprint "eagle-import:0603_CAP")
      (fields (field (name "MPN") "C1608X7S1A475K080AC"))
      (libsource (lib "eagle-import") (part "passives_20904581_CAPACITOR0603_CAP"))
    )
    (comp (ref "C54")
      (value "10uF")
      (footprint "eagle-import:SMD_1608M-0603US-C")
      (fields (field (name "MPN") "CM105X5R106M25AT"))
      (libsource (lib "eagle-import") (part "C0603US"))
    )
    (comp (ref "C55")
      (value "10uF")
      (footprint "eagle-import:SMD_1608M-0603US-C")
      (fields (field (name "MPN") "CM105X5R106M25AT"))
      (libsource (lib "eagle-import") (part "C0603US"))
    )
    (comp (ref "C90")
      (value "1uF")
      (footprint "eagle-import:0201_CAP")
      (fields (field (name "MANUFACTURER") "Murata") (field (name "MPN") "GRM033R61A105ME44D"))
      (libsource (lib "eagle-import") (part "passives_20904581_CAPACITOR0201_CAP"))
    )
    (comp (ref "C91")
      (value "1uF")
      (footprint "eagle-import:0201_CAP")
      (fields (field (name "MANUFACTURER") "Murata") (field (name "MPN") "GRM033R61A105ME44D"))
      (libsource (lib "eagle-import") (part "passives_20904581_CAPACITOR0201_CAP"))
    )
    (comp (ref "CX1")
      (value "DNP")
      (footprint "eagle-import:0603_CAP")
      (libsource (lib "eagle-import") (part "passives_20904581_CAPACITOR0603_CAP"))
    )
    (comp (ref "CX2")
      (value "DNP")
      (footprint "eagle-import:0603_CAP")
      (libsource (lib "eagle-import") (part "passives_20904581_CAPACITOR0603_CAP"))
    )
    (comp (ref "FB1")
      (value "BLM03PG330SN1D")
      (footprint "eagle-import:0201_FB")
      (fields (field (name "MANUFACTURER") "Murata"))
      (libsource (lib "eagle-import") (part "FERRITE_BEAD0201"))
    )
    (comp (ref "JP3")
      (value "JUMPER-SMT_3_1-NC_TRACE_SILK")
      (footprint "eagle-import:SMT-JUMPER_3_1-NC_TRACE_SILK")
      (libsource (lib "eagle-import") (part "JUMPER-SMT_3_1-NC_TRACE_SILK"))
    )
    (comp (ref "JP12")
      (value "JUMPER-SMT_3_1-NC_TRACE_SILK")
      (footprint "eagle-import:SMT-JUMPER_3_1-NC_TRACE_SILK")
      (libsource (lib "eagle-import") (part "JUMPER-SMT_3_1-NC_TRACE_SILK"))
    )
    (comp (ref "R1")
      (value "49.9-1%")
      (footprint "eagle-import:0201_RES")
      (fields (field (name "MPN") "ERJ-1GNF49R9C"))
      (libsource (lib "eagle-import") (part "passives_20904581_RESISTOR0201_RES"))
    )
    (comp (ref "R24")
      (value "100k")
      (footprint "eagle-import:0402_RES")
      (fields (field (name "MPN") "RT0402BRE07100KL"))
      (libsource (lib "eagle-import") (part "RESISTOR0402_RES"))
    )
    (comp (ref "RX1")
      (value "DNP")
      (footprint "eagle-import:0603-RES")
      (libsource (lib "eagle-import") (part "passives_20904581_RESISTOR0603_RES"))
    )
    (comp (ref "RZ1")
      (value "0")
      (footprint "eagle-import:0603-RES")
      (fields (field (name "MPN") "RMCF0603ZT0R00"))
      (libsource (lib "eagle-import") (part "passives_20904581_RESISTOR0603_RES"))
    )
    (comp (ref "RZ2")
      (value "0")
      (footprint "eagle-import:0603-RES")
      (fields (field (name "MPN") "RMCF0603ZT0R00"))
      (libsource (lib "eagle-import") (part "passives_20904581_RESISTOR0603_RES"))
    )
    (comp (ref "RZ4")
      (value "0")
      (footprint "eagle-import:0402_RES")
      (fields (field (name "MPN") "RMCF0402ZT0R00"))
      (libsource (lib "eagle-import") (part "passives_20904581_RESISTOR0402_RES"))
    )
    (comp (ref "S2")
      (value "SKY13373")
      (footprint "eagle-import:SKY13373")
      (fields (field (name "MANUFACTURER") "Skyworks") (field (name "MPN") "SKY13373-460LF"))
      (libsource (lib "eagle-import") (part "SKY13373"))
    )
    (comp (ref "S3")
      (value "SIP3241XSIP32414")
      (footprint "eagle-import:TDFN2X2X0P6-8")
      (fields (field (name "MANUFACTURER") "Vishay") (field (name "MPN") "SIP32414DNP-T1-GE4"))
      (libsource (lib "eagle-import") (part "SIP3241XSIP32414"))
    )
    (comp (ref "S4")
      (value "MM8030-2610")
      (footprint "eagle-import:MM8030-2610")
      (fields (field (name "MANUFACTURER") "Murata"))
      (libsource (lib "eagle-import") (part "MM8030-2610"))
    )
    (comp (ref "TP0")
      (value "TEST-POINT")
      (footprint "eagle-import:PAD.03X.03")
      (libsource (lib "eagle-import") (part "TEST-POINT"))
    )
    (comp (ref "TP1")
      (value "TEST-POINT")
      (footprint "eagle-import:PAD.03X.03")
      (libsource (lib "eagle-import") (part "TEST-POINT"))
    )
    (comp (ref "TP2")
      (value "TEST-POINT")
      (footprint "eagle-import:PAD.03X.03")
      (libsource (lib "eagle-import") (part "TEST-POINT"))
    )
    (comp (ref "TP3")
      (value "TEST-POINT")
      (footprint "eagle-import:PAD.03X.03")
      (libsource (lib "eagle-import") (part "TEST-POINT"))
    )
    (comp (ref "TP4")
      (value "TEST-POINT")
      (footprint "eagle-import:PAD.03X.03")
      (libsource (lib "eagle-import") (part "TEST-POINT"))
    )
    (comp (ref "TP5")
      (value "TEST-POINT")
      (footprint "eagle-import:PAD.03X.03")
      (libsource (lib "eagle-import") (part "TEST-POINT"))
    )
    (comp (ref "TP6")
      (value "TEST-POINT")
      (footprint "eagle-import:PAD.03X.03")
      (libsource (lib "eagle-import") (part "TEST-POINT"))
    )
    (comp (ref "TP7")
      (value "TEST-POINT")
      (footprint "eagle-import:PAD.03X.03")
      (libsource (lib "eagle-import") (part "TEST-POINT"))
    )
    (comp (ref "U2")
      (value "DW3110")
      (footprint "eagle-import:WLCSP52")
      (fields (field (name "MANUFACTURER") "Qorvo"))
      (libsource (lib "eagle-import") (part "DW3110"))
    )
    (comp (ref "U7")
      (value "QM14068")
      (footprint "eagle-import:QM14068")
      (fields (field (name "MANUFACTURER") "Qorvo"))
      (libsource (lib "eagle-import") (part "QM14068"))
    )
    (comp (ref "VR3")
      (value "TPS7A0218PDQNR")
      (footprint "eagle-import:4-XDFN-EP")
      (libsource (lib "eagle-import") (part "TPS7A0218PDQNR"))
    )
    (comp (ref "X4")
      (value "TXC-8Y")
      (footprint "eagle-import:TXC-8Y")
      (fields
        (field (name "FREQ") "38.4 MHz")
        (field (name "MANUFACTURER") "TXC")
        (field (name "MPN") "8Y38472012")
      )
      (libsource (lib "eagle-import") (part "TXC-8Y"))
    )
    (comp (ref "FD1")
      (value "FIDUCIAL")
      (footprint "eagle-import:FIDUCIAL_1MM-CU_2MM-MASK")
      (libsource (lib "eagle-import") (part "FIDUCIAL"))
    )
    (comp (ref "FD2")
      (value "FIDUCIAL")
      (footprint "eagle-import:FIDUCIAL_1MM-CU_2MM-MASK")
      (libsource (lib "eagle-import") (part "FIDUCIAL"))
    )
    (comp (ref "FD4")
      (value "FIDUCIAL")
      (footprint "eagle-import:FIDUCIAL_1MM-CU_2MM-MASK")
      (libsource (lib "eagle-import") (part "FIDUCIAL"))
    )
    (comp (ref "FD6")
      (value "FIDUCIAL")
      (footprint "eagle-import:FIDUCIAL_1MM-CU_2MM-MASK")
      (libsource (lib "eagle-import") (part "FIDUCIAL"))
    )
    (comp (ref "C5")
      (value "4pF")
      (footprint "eagle-import:0201_CAP")
      (fields (field (name "MANUFACTURER") "Murata") (field (name "MPN") "GRM0335C1H4R0BA01D"))
      (libsource (lib "eagle-import") (part "passives_20904581_CAPACITOR0201_CAP"))
    )
    (comp (ref "C6")
      (value "4pF")
      (footprint "eagle-import:0201_CAP")
      (fields (field (name "MANUFACTURER") "Murata") (field (name "MPN") "GRM0335C1H4R0BA01D"))
      (libsource (lib "eagle-import") (part "passives_20904581_CAPACITOR0201_CAP"))
    )
    (comp (ref "C31")
      (value "0.1uF")
      (footprint "eagle-import:0402_CAP")
      (fields (field (name "MPN") "CL05A104KP5NNNC"))
      (libsource (lib "eagle-import") (part "passives_20904581_CAPACITOR0402_CAP"))
    )
    (comp (ref "C32")
      (value "0.1uF")
      (footprint "eagle-import:0402_CAP")
      (fields (field (name "MPN") "CL05A104KP5NNNC"))
      (libsource (lib "eagle-import") (part "passives_20904581_CAPACITOR0402_CAP"))
    )
    (comp (ref "C35")
      (value "0.1uF")
      (footprint "eagle-import:0402_CAP")
      (fields (field (name "MPN") "CL05A104KP5NNNC"))
      (libsource (lib "eagle-import") (part "passives_20904581_CAPACITOR0402_CAP"))
    )
    (comp (ref "C36")
      (value "0.1uF")
      (footprint "eagle-import:0402_CAP")
      (fields (field (name "MPN") "CL05A104KP5NNNC"))
      (libsource (lib "eagle-import") (part "CAPACITOR0402_CAP"))
    )
    (comp (ref "C44")
      (value "1uF")
      (footprint "eagle-import:0402_CAP")
      (fields (field (name "MPN") "GRM155R70J105KA12J"))
      (libsource (lib "eagle-import") (part "CAPACITOR0402_CAP"))
    )
    (comp (ref "D4")
      (value "DIODE0402")
      (footprint "eagle-import:0402_DIODE")
      (fields (field (name "MPN") "CDSQR400B-HF"))
      (libsource (lib "eagle-import") (part "DIODE0402"))
    )
    (comp (ref "LS1")
      (value "PUI_SMT-0440-T-2-R")
      (footprint "eagle-import:SMT-0440-T-2-R")
      (fields (field (name "MPN") "SMT-0440-T-2-R"))
      (libsource (lib "eagle-import") (part "PUI_SMT-0440-T-2-R"))
    )
    (comp (ref "Q2")
      (value "MOSFET-NCHANNELXFDN-3")
      (footprint "eagle-import:XFDFN-3")
      (libsource (lib "eagle-import") (part "MOSFET-NCHANNELXFDN-3"))
    )
    (comp (ref "R12")
      (value "10k")
      (footprint "eagle-import:0402_RES")
      (fields (field (name "MPN") "RC0402JR-0710KL"))
      (libsource (lib "eagle-import") (part "RESISTOR0402_RES"))
    )
    (comp (ref "R16")
      (value "10k")
      (footprint "eagle-import:0402_RES")
      (fields (field (name "MPN") "RC0402JR-0710KL"))
      (libsource (lib "eagle-import") (part "RESISTOR0402_RES"))
    )
    (comp (ref "R20")
      (value "10k")
      (footprint "eagle-import:0402_RES")
      (fields (field (name "MPN") "RC0402JR-0710KL"))
      (libsource (lib "eagle-import") (part "RESISTOR0402_RES"))
    )
    (comp (ref "R25")
      (value "100k")
      (footprint "eagle-import:0402_RES")
      (fields (field (name "MPN") "RT0402BRE07100KL"))
      (libsource (lib "eagle-import") (part "RESISTOR0402_RES"))
    )
    (comp (ref "RX2")
      (value "DNP")
      (footprint "eagle-import:0603-RES")
      (libsource (lib "eagle-import") (part "passives_20904581_RESISTOR0603_RES"))
    )
    (comp (ref "RX5")
      (value "DNP")
      (footprint "eagle-import:0603-RES")
      (libsource (lib "eagle-import") (part "passives_20904581_RESISTOR0603_RES"))
    )
    (comp (ref "RX6")
      (value "DNP")
      (footprint "eagle-import:0603-RES")
      (libsource (lib "eagle-import") (part "passives_20904581_RESISTOR0603_RES"))
    )
    (comp (ref "RX8")
      (value "DNP")
      (footprint "eagle-import:0603-RES")
      (libsource (lib "eagle-import") (part "passives_20904581_RESISTOR0603_RES"))
    )
    (comp (ref "RX9")
      (value "DNP")
      (footprint "eagle-import:0603-RES")
      (libsource (lib "eagle-import") (part "passives_20904581_RESISTOR0603_RES"))
    )
    (comp (ref "RZ12")
      (value "0")
      (footprint "eagle-import:0402_RES")
      (fields (field (name "MPN") "RMCF0402ZT0R00"))
      (libsource (lib "eagle-import") (part "passives_20904581_RESISTOR0402_RES"))
    )
    (comp (ref "U6")
      (value "BNO086")
      (footprint "eagle-import:LGA28R0P510X4_5P2X3P8X1")
      (fields (field (name "MANUFACTURER") "CEVA Technologies, Inc."))
      (libsource (lib "eagle-import") (part "BNO086"))
    )
    (comp (ref "U8")
      (value "AS5FXXX04SND")
      (footprint "eagle-import:AS5FXXXXXXXX-XXLXN")
      (fields (field (name "MANUFACTURER") "Alliance Memory") (field (name "MPN") "AS5F18G04SND-10LIN"))
      (libsource (lib "eagle-import") (part "AS5FXXX04SND"))
    )
    (comp (ref "X2")
      (value "TXC-9HT12")
      (footprint "eagle-import:TXC-9HT12")
      (fields
        (field (name "C-LOAD") "7pF")
        (field (name "FREQUENCY") "32.768 kHz")
        (field (name "MANUFACTURER") "TXC Corp")
        (field (name "MPN") "9HT12-32.768KDZY-T")
      )
      (libsource (lib "eagle-import") (part "TXC-9HT12"))
    )
    (comp (ref "A4")
      (value "AMCA72-2R47G-S1F-T")
      (footprint "eagle-import:AMCA72-2R470G-S1F-T")
      (fields (field (name "MPN") "AMCA72-2R470G-S1F-T4"))
      (libsource (lib "eagle-import") (part "AMCA72-2R47G-S1F-T"))
    )
    (comp (ref "C1")
      (value "1.5pF")
      (footprint "eagle-import:CAPC1005X60")
      (description "CAP CER 1.5PF 50V C0G/NP0 0402")
      (fields
        (field (name "MANUFACTURER") "KEMET")
        (field (name "MPN") "C0402C159C5GACTU")
        (field (name "TEMPCOEFF") "NP0")
        (field (name "TOLERANCE") "+/- 0.25pF")
      )
      (libsource (lib "eagle-import") (part "CCHIP-0402(1005-METRIC)_"))
    )
    (comp (ref "C58")
      (value "2.2uF")
      (footprint "eagle-import:0201_CAP")
      (fields (field (name "MANUFACTURER") "Murata") (field (name "MPN") "GRM033R61A225KE47D"))
      (libsource (lib "eagle-import") (part "passives_20904581_CAPACITOR0201_CAP"))
    )
    (comp (ref "C59")
      (value "2.2uF")
      (footprint "eagle-import:0201_CAP")
      (fields (field (name "MANUFACTURER") "Murata") (field (name "MPN") "GRM033R61A225KE47D"))
      (libsource (lib "eagle-import") (part "passives_20904581_CAPACITOR0201_CAP"))
    )
    (comp (ref "C60")
      (value "2.2uF")
      (footprint "eagle-import:0201_CAP")
      (fields (field (name "MANUFACTURER") "Murata") (field (name "MPN") "GRM033R61A225KE47D"))
      (libsource (lib "eagle-import") (part "passives_20904581_CAPACITOR0201_CAP"))
    )
    (comp (ref "C61")
      (value "2.2uF")
      (footprint "eagle-import:0201_CAP")
      (fields (field (name "MANUFACTURER") "Murata") (field (name "MPN") "GRM033R61A225KE47D"))
      (libsource (lib "eagle-import") (part "passives_20904581_CAPACITOR0201_CAP"))
    )
    (comp (ref "C62")
      (value "1uF")
      (footprint "eagle-import:0201_CAP")
      (fields (field (name "MANUFACTURER") "Murata") (field (name "MPN") "GRM033R61A105ME44D"))
      (libsource (lib "eagle-import") (part "passives_20904581_CAPACITOR0201_CAP"))
    )
    (comp (ref "C63")
      (value "1uF")
      (footprint "eagle-import:0201_CAP")
      (fields (field (name "MANUFACTURER") "Murata") (field (name "MPN") "GRM033R61A105ME44D"))
      (libsource (lib "eagle-import") (part "passives_20904581_CAPACITOR0201_CAP"))
    )
    (comp (ref "C64")
      (value "1uF")
      (footprint "eagle-import:0201_CAP")
      (fields (field (name "MANUFACTURER") "Murata") (field (name "MPN") "GRM033R61A105ME44D"))
      (libsource (lib "eagle-import") (part "passives_20904581_CAPACITOR0201_CAP"))
    )
    (comp (ref "C65")
      (value "1uF")
      (footprint "eagle-import:0201_CAP")
      (fields (field (name "MANUFACTURER") "Murata") (field (name "MPN") "GRM033R61A105ME44D"))
      (libsource (lib "eagle-import") (part "passives_20904581_CAPACITOR0201_CAP"))
    )
    (comp (ref "C66")
      (value "2.2uF")
      (footprint "eagle-import:0201_CAP")
      (fields (field (name "MANUFACTURER") "Murata") (field (name "MPN") "GRM033R61A225KE47D"))
      (libsource (lib "eagle-import") (part "passives_20904581_CAPACITOR0201_CAP"))
    )
    (comp (ref "C67")
      (value "2.2uF")
      (footprint "eagle-import:0201_CAP")
      (fields (field (name "MANUFACTURER") "Murata") (field (name "MPN") "GRM033R61A225KE47D"))
      (libsource (lib "eagle-import") (part "passives_20904581_CAPACITOR0201_CAP"))
    )
    (comp (ref "C69")
      (value "4.7uF")
      (footprint "eagle-import:0402_CAP")
      (fields (field (name "MPN") "CL05A475MP5NRNC"))
      (libsource (lib "eagle-import") (part "CAPACITOR0402_CAP"))
    )
    (comp (ref "C70")
      (value "2.2uF")
      (footprint "eagle-import:0201_CAP")
      (fields (field (name "MANUFACTURER") "Murata") (field (name "MPN") "GRM033R61A225KE47D"))
      (libsource (lib "eagle-import") (part "passives_20904581_CAPACITOR0201_CAP"))
    )
    (comp (ref "C71")
      (value "2.2uF")
      (footprint "eagle-import:0201_CAP")
      (fields (field (name "MANUFACTURER") "Murata") (field (name "MPN") "GRM033R61A225KE47D"))
      (libsource (lib "eagle-import") (part "passives_20904581_CAPACITOR0201_CAP"))
    )
    (comp (ref "C72")
      (value "2.2uF")
      (footprint "eagle-import:0201_CAP")
      (fields (field (name "MANUFACTURER") "Murata") (field (name "MPN") "GRM033R61A225KE47D"))
      (libsource (lib "eagle-import") (part "passives_20904581_CAPACITOR0201_CAP"))
    )
    (comp (ref "C73")
      (value "2.2uF")
      (footprint "eagle-import:0201_CAP")
      (fields (field (name "MANUFACTURER") "Murata") (field (name "MPN") "GRM033R61A225KE47D"))
      (libsource (lib "eagle-import") (part "passives_20904581_CAPACITOR0201_CAP"))
    )
    (comp (ref "C74")
      (value "2.2uF")
      (footprint "eagle-import:0201_CAP")
      (fields (field (name "MANUFACTURER") "Murata") (field (name "MPN") "GRM033R61A225KE47D"))
      (libsource (lib "eagle-import") (part "passives_20904581_CAPACITOR0201_CAP"))
    )
    (comp (ref "C75")
      (value "2.2uF")
      (footprint "eagle-import:0201_CAP")
      (fields (field (name "MANUFACTURER") "Murata") (field (name "MPN") "GRM033R61A225KE47D"))
      (libsource (lib "eagle-import") (part "passives_20904581_CAPACITOR0201_CAP"))
    )
    (comp (ref "C76")
      (value "4700pF")
      (footprint "eagle-import:CAPC1005X60")
      (fields (field (name "MPN") "KGM05AR71E472KH"))
      (libsource (lib "eagle-import") (part "CCHIP-0402(1005-METRIC)_"))
    )
    (comp (ref "C79")
      (value "1uF")
      (footprint "eagle-import:0201_CAP")
      (fields (field (name "MANUFACTURER") "MURATA") (field (name "MPN") "GRM033R61A105ME44D"))
      (libsource (lib "eagle-import") (part "passives_20904581_CAPACITOR0201_CAP"))
    )
    (comp (ref "C80")
      (value "6pF")
      (footprint "eagle-import:CAPC1005X60")
      (fields (field (name "MANUFACTURER") "Murata") (field (name "MPN") "GCM1555C1H6R0BA16D"))
      (libsource (lib "eagle-import") (part "CCHIP-0402(1005-METRIC)_"))
    )
    (comp (ref "C81")
      (value "6pF")
      (footprint "eagle-import:CAPC1005X60")
      (fields (field (name "MANUFACTURER") "Murata") (field (name "MPN") "GCM1555C1H6R0BA16D"))
      (libsource (lib "eagle-import") (part "CCHIP-0402(1005-METRIC)_"))
    )
    (comp (ref "C93")
      (value "1uF")
      (footprint "eagle-import:0201_CAP")
      (fields (field (name "MANUFACTURER") "Murata") (field (name "MPN") "GRM033R61A105ME44D"))
      (libsource (lib "eagle-import") (part "passives_20904581_CAPACITOR0201_CAP"))
    )
    (comp (ref "CX3")
      (value "DNP")
      (footprint "eagle-import:CAPC1005X60")
      (libsource (lib "eagle-import") (part "CCHIP-0402(1005-METRIC)_"))
    )
    (comp (ref "CX4")
      (value "DNP")
      (footprint "eagle-import:CAPC1005X60")
      (libsource (lib "eagle-import") (part "CCHIP-0402(1005-METRIC)_"))
    )
    (comp (ref "CX5")
      (value "DNP")
      (footprint "eagle-import:CAPC1005X60")
      (libsource (lib "eagle-import") (part "CCHIP-0402(1005-METRIC)_"))
    )
    (comp (ref "D3")
      (value "ZENER")
      (footprint "eagle-import:SODFL1608X70")
      (description "DIODE TVS 5.5V STANDOFF 8V BREAKDOWN SC79")
      (fields (field (name "MANUFACTURER") "NXP SEMICONDUCTOR") (field (name "MPN") "PESD5V0X1UB,135"))
      (libsource (lib "eagle-import") (part "ZENERSODFL(1608-METRIC)_"))
    )
    (comp (ref "L5")
      (value "2.2µH")
      (footprint "eagle-import:0805_CAP")
      (fields (field (name "MANUFACTURER") "Murata") (field (name "MPN") "DFE201210U-2R2M=P2"))
      (libsource (lib "eagle-import") (part "INDUCTOR0805"))
    )
    (comp (ref "L6")
      (value "1.0µH")
      (footprint "eagle-import:0603_CAP")
      (fields (field (name "MANUFACTURER") "Murata") (field (name "MPN") "DFE18SAN1R0ME0L"))
      (libsource (lib "eagle-import") (part "INDUCTOR0603"))
    )
    (comp (ref "L7")
      (value "2.0nH")
      (footprint "eagle-import:INDC1006X60N")
      (description "FIXED IND 2.0NH0.1NH SMD")
      (fields
        (field (name "MANUFACTURER") "Murata")
        (field (name "MPN") "LQG15HS2N0B02D")
        (field (name "TOLERANCE") "+/- 0.1 nH")
      )
      (libsource (lib "eagle-import") (part "LCHIP-0402(1006-METRIC)_"))
    )
    (comp (ref "L8")
      (value "2.2nH")
      (footprint "eagle-import:INDC1006X60N")
      (description "FIXED IND 2.2NH0.1NH SMD")
      (fields
        (field (name "MANUFACTURER") "Murata")
        (field (name "MPN") "LQG15HN2N2B02D")
        (field (name "TOLERANCE") "+/- 0.1 nH")
      )
      (libsource (lib "eagle-import") (part "LCHIP-0402(1006-METRIC)_"))
    )
    (comp (ref "RZ9")
      (value "0")
      (footprint "eagle-import:0402_RES")
      (fields (field (name "MPN") "RMCF0402ZT0R00"))
      (libsource (lib "eagle-import") (part "passives_20904581_RESISTOR0402_RES"))
    )
    (comp (ref "TP8")
      (value "VDDBH")
      (footprint "eagle-import:PAD.03X.03")
      (libsource (lib "eagle-import") (part "TEST-POINT"))
    )
    (comp (ref "TP9")
      (value "VDDP")
      (footprint "eagle-import:PAD.03X.03")
      (libsource (lib "eagle-import") (part "TEST-POINT"))
    )
    (comp (ref "TP10")
      (value "VDDF")
      (footprint "eagle-import:PAD.03X.03")
      (libsource (lib "eagle-import") (part "TEST-POINT"))
    )
    (comp (ref "U1")
      (value "APOLLO4_BLUE_PLUS_SOC_KBR")
      (footprint "eagle-import:APOLLO4_BLUE_SOC_BGA")
      (fields (field (name "MANUFACTURER") "Ambiq") (field (name "MPN") "AMA4B2KP-KBR"))
      (libsource (lib "eagle-import") (part "APOLLO4_BLUE_PLUS_SOC_KBR"))
    )
    (comp (ref "X1")
      (value "ABM12W")
      (footprint "eagle-import:ABM12W")
      (fields
        (field (name "C-LOAD") "6pF")
        (field (name "FREQUENCY") "32 MHz")
        (field (name "MANUFACTURER") "Abracon")
        (field (name "MAX-ESR") "80Ω")
        (field (name "MPN") "ABM12W-32.0000MHZ-6-D1X-T3")
      )
      (libsource (lib "eagle-import") (part "ABM12W"))
    )
    (comp (ref "X3")
      (value "TXC-9HT12")
      (footprint "eagle-import:TXC-9HT12")
      (fields
        (field (name "C-LOAD") "7pF")
        (field (name "FREQUENCY") "32.768 kHz")
        (field (name "MANUFACTURER") "TXC Corp")
        (field (name "MPN") "9HT12-32.768KDZY-T")
      )
      (libsource (lib "eagle-import") (part "TXC-9HT12"))
    )
  )
  (nets
    (net (code "1") (name "+1V8") (class "Default")
      (node (ref "C26") (pin "1") (pinfunction "1_1") (pintype "bidirectional"))
      (node (ref "C31") (pin "1") (pinfunction "1_1") (pintype "bidirectional"))
      (node (ref "C35") (pin "1") (pinfunction "1_1") (pintype "bidirectional"))
      (node (ref "C46") (pin "1") (pinfunction "1_1") (pintype "bidirectional"))
      (node (ref "C50") (pin "2") (pinfunction "2_2") (pintype "bidirectional"))
      (node (ref "C62") (pin "P$1") (pinfunction "1_P$1") (pintype "bidirectional"))
      (node (ref "C63") (pin "P$1") (pinfunction "1_P$1") (pintype "bidirectional"))
      (node (ref "C64") (pin "P$1") (pinfunction "1_P$1") (pintype "bidirectional"))
      (node (ref "C65") (pin "P$1") (pinfunction "1_P$1") (pintype "bidirectional"))
      (node (ref "C66") (pin "P$1") (pinfunction "1_P$1") (pintype "bidirectional"))
      (node (ref "C67") (pin "P$1") (pinfunction "1_P$1") (pintype "bidirectional"))
      (node (ref "C75") (pin "P$2") (pinfunction "2_P$2") (pintype "bidirectional"))
      (node (ref "C8") (pin "P$2") (pinfunction "2_P$2") (pintype "bidirectional"))
      (node (ref "J1") (pin "1") (pinfunction "VTREF_1") (pintype "bidirectional"))
      (node (ref "J1") (pin "B1") (pinfunction "VTREF_B1") (pintype "bidirectional"))
      (node (ref "JP1") (pin "2") (pinfunction "2_2") (pintype "passive"))
      (node (ref "JP11") (pin "1") (pinfunction "1_1") (pintype "passive"))
      (node (ref "JP12") (pin "1") (pinfunction "1_1") (pintype "passive"))
      (node (ref "L2") (pin "P$1") (pinfunction "1_P$1") (pintype "bidirectional"))
      (node (ref "R12") (pin "2") (pinfunction "2_2") (pintype "passive"))
      (node (ref "R16") (pin "2") (pinfunction "2_2") (pintype "passive"))
      (node (ref "R20") (pin "2") (pinfunction "2_2") (pintype "passive"))
      (node (ref "R29") (pin "1") (pinfunction "1_1") (pintype "passive"))
      (node (ref "RX2") (pin "2") (pinfunction "2_2") (pintype "passive"))
      (node (ref "RX5") (pin "1") (pinfunction "1_1") (pintype "passive"))
      (node (ref "RX6") (pin "1") (pinfunction "1_1") (pintype "passive"))
      (node (ref "RX8") (pin "2") (pinfunction "2_2") (pintype "passive"))
      (node (ref "RZ12") (pin "2") (pinfunction "2_2") (pintype "passive"))
      (node (ref "S3") (pin "4") (pinfunction "IN_4") (pintype "bidirectional"))
      (node (ref "TP9") (pin "P$1") (pinfunction "TESTPOINT_P$1") (pintype "bidirectional"))
      (node (ref "U1") (pin "B1") (pinfunction "VDDP-IO_PAD_SUP_B1") (pintype "bidirectional"))
      (node (ref "U1") (pin "C4") (pinfunction "VDDA-ANALOG_SUP_C4") (pintype "bidirectional"))
      (node (ref "U1") (pin "E11") (pinfunction "VDDAUDD_E11") (pintype "bidirectional"))
      (node (ref "U1") (pin "G1") (pinfunction "VDDB-BLE_SUPPLY_G1") (pintype "bidirectional"))
      (node (ref "U1") (pin "M10") (pinfunction "VDDH-HV_SUP_M10") (pintype "bidirectional"))
      (node (ref "U1") (pin "M9") (pinfunction "VDDH2-HV_SUP_M9") (pintype "bidirectional"))
      (node (ref "U2") (pin "B13") (pinfunction "VDD1_B13") (pintype "bidirectional"))
      (node (ref "U6") (pin "28") (pinfunction "VDDIO_28") (pintype "input"))
      (node (ref "U8") (pin "8") (pinfunction "VCC_8") (pintype "bidirectional"))
    )
    (net (code "2") (name "+2V5") (class "Default")
      (node (ref "C32") (pin "1") (pinfunction "1_1") (pintype "bidirectional"))
      (node (ref "C34") (pin "1") (pinfunction "1_1") (pintype "bidirectional"))
      (node (ref "C44") (pin "1") (pinfunction "1_1") (pintype "bidirectional"))
      (node (ref "C47") (pin "2") (pinfunction "2_2") (pintype "bidirectional"))
      (node (ref "C49") (pin "1") (pinfunction "1_1") (pintype "bidirectional"))
      (node (ref "C7") (pin "P$1") (pinfunction "1_P$1") (pintype "bidirectional"))
      (node (ref "C77") (pin "P$1") (pinfunction "1_P$1") (pintype "bidirectional"))
      (node (ref "C90") (pin "P$1") (pinfunction "1_P$1") (pintype "bidirectional"))
      (node (ref "D4") (pin "CATHODE") (pinfunction "CATHODE_CATHODE") (pintype "bidirectional"))
      (node (ref "JP10") (pin "1") (pinfunction "1_1") (pintype "passive"))
      (node (ref "L1") (pin "P$2") (pinfunction "2_P$2") (pintype "bidirectional"))
      (node (ref "LS1") (pin "+") (pinfunction "P_+") (pintype "passive"))
      (node (ref "R28") (pin "2") (pinfunction "2_2") (pintype "passive"))
      (node (ref "RX1") (pin "1") (pinfunction "1_1") (pintype "passive"))
      (node (ref "RZ10") (pin "1") (pinfunction "1_1") (pintype "passive"))
      (node (ref "S2") (pin "6") (pinfunction "VDD_6") (pintype "power_in"))
      (node (ref "S3") (pin "1") (pinfunction "IN_1") (pintype "bidirectional"))
      (node (ref "U6") (pin "3") (pinfunction "VDD_3") (pintype "input"))
      (node (ref "VR2") (pin "4") (pinfunction "IN_4") (pintype "bidirectional"))
      (node (ref "VR3") (pin "4") (pinfunction "IN_4") (pintype "bidirectional"))
    )
    (net (code "3") (name "AGND") (class "Default")
      (node (ref "C1") (pin "2") (pinfunction "2_2") (pintype "passive"))
      (node (ref "C93") (pin "P$2") (pinfunction "2_P$2") (pintype "bidirectional"))
      (node (ref "CX5") (pin "2") (pinfunction "2_2") (pintype "passive"))
      (node (ref "U1") (pin "M1") (pinfunction "RFIOM_M1") (pintype "bidirectional"))
      (node (ref "U1") (pin "M3") (pinfunction "RFSUB-RF_SUBSTRATE_GND_M3") (pintype "bidirectional"))
    )
    (net (code "4") (name "ANT1") (class "Default")
      (node (ref "A1") (pin "FEED") (pinfunction "ANTENNA_FEED") (pintype "bidirectional"))
      (node (ref "U7") (pin "2") (pinfunction "LNA_IN_2") (pintype "bidirectional"))
    )
    (net (code "5") (name "AP4_GP06{slash}TT_FLASH_~{HOLD_IO3}") (class "Default")
      (node (ref "U1") (pin "J5") (pinfunction "GPIO6_J5") (pintype "bidirectional"))
      (node (ref "U8") (pin "7") (pinfunction "~{HOLD}/SIO3_7") (pintype "bidirectional"))
    )
    (net (code "6") (name "AP4_GP08{slash}TT_9DOF_H_SCL{slash}SCK{slash}RX") (class "Default")
      (node (ref "RX6") (pin "2") (pinfunction "2_2") (pintype "passive"))
      (node (ref "U1") (pin "H2") (pinfunction "GPIO31_H2") (pintype "bidirectional"))
      (node (ref "U6") (pin "19") (pinfunction "H_SCL/SCK/RX_19") (pintype "bidirectional"))
    )
    (net (code "7") (name "AP4_GP09{slash}TT_9DOF_H_SDA{slash}H_MISO{slash}TX") (class "Default")
      (node (ref "RX5") (pin "2") (pinfunction "2_2") (pintype "passive"))
      (node (ref "U1") (pin "G2") (pinfunction "GPIO32_G2") (pintype "bidirectional"))
      (node (ref "U6") (pin "20") (pinfunction "H_SDA/H_MISO/TX_20") (pintype "bidirectional"))
    )
    (net (code "8") (name "AP4_GP10{slash}TT_9DOF_SA0{slash}H_MOSI") (class "Default")
      (node (ref "U1") (pin "G3") (pinfunction "GPIO33_G3") (pintype "bidirectional"))
      (node (ref "U6") (pin "17") (pinfunction "SA0/H_MOSI_17") (pintype "input"))
    )
    (net (code "9") (name "AP4_GP13{slash}TT_9DOF_~{BOOT}") (class "Default")
      (node (ref "R20") (pin "1") (pinfunction "1_1") (pintype "passive"))
      (node (ref "U1") (pin "D5") (pinfunction "GPIO13_D5") (pintype "bidirectional"))
      (node (ref "U6") (pin "4") (pinfunction "~{BOOT}_4") (pintype "input"))
    )
    (net (code "10") (name "AP4_GP14{slash}TT_~{DW_SPI_CS}") (class "Default")
      (node (ref "U1") (pin "D6") (pinfunction "GPIO14_D6") (pintype "bidirectional"))
      (node (ref "U2") (pin "B5") (pinfunction "~{SPICS}_B5") (pintype "bidirectional"))
    )
    (net (code "11") (name "AP4_GP17{slash}TT_9DOF_H_~{INT}") (class "Default")
      (node (ref "U1") (pin "D4") (pinfunction "GPIO17_D4") (pintype "bidirectional"))
      (node (ref "U6") (pin "14") (pinfunction "H_INTN_14") (pintype "output"))
    )
    (net (code "12") (name "AP4_GP18{slash}TT_BATIN") (class "Default")
      (node (ref "C27") (pin "1") (pinfunction "1_1") (pintype "bidirectional"))
      (node (ref "R30") (pin "2") (pinfunction "2_2") (pintype "passive"))
      (node (ref "R31") (pin "1") (pinfunction "1_1") (pintype "passive"))
      (node (ref "U1") (pin "D3") (pinfunction "GPIO18_D3") (pintype "bidirectional"))
    )
    (net (code "13") (name "AP4_GP24{slash}TT_RFSW_V1") (class "Default")
      (node (ref "CX2") (pin "1") (pinfunction "1_1") (pintype "bidirectional"))
      (node (ref "S2") (pin "4") (pinfunction "V1_4") (pintype "input"))
      (node (ref "U1") (pin "E2") (pinfunction "GPIO24_E2") (pintype "bidirectional"))
    )
    (net (code "14") (name "AP4_GP25{slash}TT_RFSW_V2") (class "Default")
      (node (ref "CX1") (pin "1") (pinfunction "1_1") (pintype "bidirectional"))
      (node (ref "S2") (pin "5") (pinfunction "V2_5") (pintype "input"))
      (node (ref "U1") (pin "K5") (pinfunction "GPIO25_K5") (pintype "bidirectional"))
    )
    (net (code "15") (name "AP4_GP26{slash}TT_DW_WAKEUP") (class "Default")
      (node (ref "U1") (pin "L5") (pinfunction "GPIO26_L5") (pintype "bidirectional"))
      (node (ref "U2") (pin "B9") (pinfunction "WAKEUP_B9") (pintype "bidirectional"))
    )
    (net (code "16") (name "AP4_GP27{slash}TT_DW_IRQ") (class "Default")
      (node (ref "R24") (pin "2") (pinfunction "2_2") (pintype "passive"))
      (node (ref "U1") (pin "M5") (pinfunction "GPIO27_M5") (pintype "bidirectional"))
      (node (ref "U2") (pin "B1") (pinfunction "IRQ/GPIO8_B1") (pintype "bidirectional"))
    )
    (net (code "17") (name "AP4_GP30{slash}TT_FLASH_~{WP}") (class "Default")
      (node (ref "U1") (pin "G4") (pinfunction "GPIO30_G4") (pintype "bidirectional"))
      (node (ref "U8") (pin "3") (pinfunction "~{WP}/SIO2_3") (pintype "bidirectional"))
    )
    (net (code "18") (name "AP4_GP31{slash}TT_DW_SPI_CLK") (class "Default")
      (node (ref "U1") (pin "E8") (pinfunction "GPIO8_E8") (pintype "bidirectional"))
      (node (ref "U2") (pin "A8") (pinfunction "SPICLK_A8") (pintype "bidirectional"))
    )
    (net (code "19") (name "AP4_GP32{slash}TT_DW_SPI_IO0") (class "Default")
      (node (ref "U1") (pin "E7") (pinfunction "GPIO9_E7") (pintype "bidirectional"))
      (node (ref "U2") (pin "B7") (pinfunction "SPICDI(MOSI)_B7") (pintype "bidirectional"))
    )
    (net (code "20") (name "AP4_GP33{slash}TT_DW_SPI_IO1") (class "Default")
      (node (ref "U1") (pin "E6") (pinfunction "GPIO10_E6") (pintype "bidirectional"))
      (node (ref "U2") (pin "A6") (pinfunction "SPICDO(MISO)_A6") (pintype "bidirectional"))
    )
    (net (code "21") (name "AP4_GP47{slash}TT_FLASH_SCK") (class "Default")
      (node (ref "U1") (pin "F1") (pinfunction "GPIO47_F1") (pintype "bidirectional"))
      (node (ref "U8") (pin "6") (pinfunction "SCLK_6") (pintype "input"))
    )
    (net (code "22") (name "AP4_GP48{slash}TT_FLASH_PDI_IO0") (class "Default")
      (node (ref "U1") (pin "E1") (pinfunction "GPIO48_E1") (pintype "bidirectional"))
      (node (ref "U8") (pin "5") (pinfunction "SI/SIO0_5") (pintype "bidirectional"))
    )
    (net (code "23") (name "AP4_GP49{slash}TT_FLASH_PDO_IO1") (class "Default")
      (node (ref "U1") (pin "D1") (pinfunction "GPIO49_D1") (pintype "bidirectional"))
      (node (ref "U8") (pin "2") (pinfunction "SO/SIO1_2") (pintype "bidirectional"))
    )
    (net (code "24") (name "AP4_GP50{slash}TT_~{DW_RESET}") (class "Default")
      (node (ref "U1") (pin "A9") (pinfunction "GPIO50_A9") (pintype "bidirectional"))
      (node (ref "U2") (pin "A10") (pinfunction "~{RST}_A10") (pintype "bidirectional"))
    )
    (net (code "25") (name "AP4_GP51{slash}LED1_GREEN") (class "Default")
      (node (ref "R2") (pin "2") (pinfunction "2_2") (pintype "passive"))
      (node (ref "U1") (pin "B9") (pinfunction "GPIO51_B9") (pintype "bidirectional"))
    )
    (net (code "26") (name "AP4_GP53{slash}LED1_RED") (class "Default")
      (node (ref "R5") (pin "2") (pinfunction "2_2") (pintype "passive"))
      (node (ref "U1") (pin "C9") (pinfunction "GPIO53_C9") (pintype "bidirectional"))
    )
    (net (code "27") (name "AP4_GP55{slash}TT_BUZZER_GATE") (class "Default")
      (node (ref "Q2") (pin "G") (pinfunction "G_G") (pintype "passive"))
      (node (ref "R25") (pin "1") (pinfunction "1_1") (pintype "passive"))
      (node (ref "U1") (pin "D9") (pinfunction "GPIO55_D9") (pintype "bidirectional"))
    )
    (net (code "28") (name "AP4_GP58{slash}TT_~{CHG}") (class "Default")
      (node (ref "U1") (pin "J7") (pinfunction "GPIO58_J7") (pintype "bidirectional"))
      (node (ref "U3") (pin "8") (pinfunction "~{CHG}_8") (pintype "bidirectional"))
      (node (ref "U4") (pin "7") (pinfunction "~{CHG}_7") (pintype "bidirectional"))
    )
    (net (code "29") (name "AP4_GP60{slash}TT_~{PG}") (class "Default")
      (node (ref "U1") (pin "K8") (pinfunction "GPIO60_K8") (pintype "bidirectional"))
      (node (ref "U3") (pin "5") (pinfunction "~{PG}_5") (pintype "bidirectional"))
    )
    (net (code "30") (name "AP4_GP63{slash}TT_9DOF_PS0{slash}WAKE") (class "Default")
      (node (ref "U1") (pin "M6") (pinfunction "GPIO63_M6") (pintype "bidirectional"))
      (node (ref "U6") (pin "6") (pinfunction "PS0/WAKE_6") (pintype "input"))
    )
    (net (code "31") (name "AP4_GP65{slash}TT_9DOF_~{RESET}") (class "Default")
      (node (ref "RX8") (pin "1") (pinfunction "1_1") (pintype "passive"))
      (node (ref "U1") (pin "A7") (pinfunction "GPIO65_A7") (pintype "bidirectional"))
      (node (ref "U6") (pin "11") (pinfunction "~{RESET}_11") (pintype "input"))
    )
    (net (code "32") (name "AP4_GP66{slash}TT_QI_TS_CTRL") (class "Default")
      (node (ref "C30") (pin "1") (pinfunction "1_1") (pintype "bidirectional"))
      (node (ref "RT1") (pin "2") (pinfunction "2_2") (pintype "passive"))
      (node (ref "U1") (pin "A8") (pinfunction "GPIO66_A8") (pintype "bidirectional"))
      (node (ref "U4") (pin "13") (pinfunction "TS/CTRL_13") (pintype "bidirectional"))
    )
    (net (code "33") (name "AP4_GP69{slash}TT_FLASH_~{CS}") (class "Default")
      (node (ref "RX2") (pin "1") (pinfunction "1_1") (pintype "passive"))
      (node (ref "U1") (pin "B8") (pinfunction "GPIO69_B8") (pintype "bidirectional"))
      (node (ref "U8") (pin "1") (pinfunction "~{CS}_1") (pintype "input"))
    )
    (net (code "34") (name "AP4_GP72{slash}TT_9DOF_H_~{CS}") (class "Default")
      (node (ref "U1") (pin "C8") (pinfunction "GPIO72_C8") (pintype "bidirectional"))
      (node (ref "U6") (pin "18") (pinfunction "H_~{CS}_18") (pintype "input"))
    )
    (net (code "35") (name "AP4_GP79{slash}LED2_RED") (class "Default")
      (node (ref "R4") (pin "2") (pinfunction "2_2") (pintype "passive"))
      (node (ref "U1") (pin "M11") (pinfunction "GPIO79_M11") (pintype "bidirectional"))
    )
    (net (code "36") (name "AP4_GP80{slash}SWTRACE0") (class "Default")
      (node (ref "J2") (pin "2") (pinfunction "SWDIO_2") (pintype "bidirectional"))
      (node (ref "J2") (pin "B2") (pinfunction "SWDIO_B2") (pintype "bidirectional"))
      (node (ref "U1") (pin "K10") (pinfunction "GPIO80_K10") (pintype "bidirectional"))
    )
    (net (code "37") (name "AP4_GP81{slash}SWTRACE1") (class "Default")
      (node (ref "J2") (pin "4") (pinfunction "SWDCLK_4") (pintype "bidirectional"))
      (node (ref "J2") (pin "B4") (pinfunction "SWDCLK_B4") (pintype "bidirectional"))
      (node (ref "U1") (pin "L10") (pinfunction "GPIO81_L10") (pintype "bidirectional"))
    )
    (net (code "38") (name "AP4_GP82{slash}SWTRACE2") (class "Default")
      (node (ref "J2") (pin "6") (pinfunction "SWO_6") (pintype "bidirectional"))
      (node (ref "J2") (pin "B6") (pinfunction "SWO_B6") (pintype "bidirectional"))
      (node (ref "U1") (pin "L9") (pinfunction "GPIO82_L9") (pintype "bidirectional"))
    )
    (net (code "39") (name "AP4_GP83{slash}SWTRACE3") (class "Default")
      (node (ref "J2") (pin "3") (pinfunction "~{RESET}_3") (pintype "bidirectional"))
      (node (ref "J2") (pin "B3") (pinfunction "~{RESET}_B3") (pintype "bidirectional"))
      (node (ref "U1") (pin "K9") (pinfunction "GPIO83_K9") (pintype "bidirectional"))
    )
    (net (code "40") (name "AP4_GP88{slash}LED2_YLW") (class "Default")
      (node (ref "R3") (pin "2") (pinfunction "2_2") (pintype "passive"))
      (node (ref "U1") (pin "F9") (pinfunction "GPIO88_F9") (pintype "bidirectional"))
    )
    (net (code "41") (name "AP4_SWDCLK") (class "Default")
      (node (ref "J1") (pin "4") (pinfunction "SWDCLK_4") (pintype "bidirectional"))
      (node (ref "J1") (pin "B4") (pinfunction "SWDCLK_B4") (pintype "bidirectional"))
      (node (ref "U1") (pin "K3") (pinfunction "GPIO20_K3") (pintype "bidirectional"))
    )
    (net (code "42") (name "AP4_SWDIO") (class "Default")
      (node (ref "J1") (pin "2") (pinfunction "SWDIO_2") (pintype "bidirectional"))
      (node (ref "J1") (pin "B2") (pinfunction "SWDIO_B2") (pintype "bidirectional"))
      (node (ref "U1") (pin "J3") (pinfunction "GPIO21_J3") (pintype "bidirectional"))
    )
    (net (code "43") (name "AP4_SWO") (class "Default")
      (node (ref "J1") (pin "6") (pinfunction "SWO_6") (pintype "bidirectional"))
      (node (ref "J1") (pin "B6") (pinfunction "SWO_B6") (pintype "bidirectional"))
      (node (ref "U1") (pin "L4") (pinfunction "GPIO3_L4") (pintype "bidirectional"))
    )
    (net (code "44") (name "AP4_SWTRACECLK") (class "Default")
      (node (ref "J2") (pin "1") (pinfunction "VTREF_1") (pintype "bidirectional"))
      (node (ref "J2") (pin "B1") (pinfunction "VTREF_B1") (pintype "bidirectional"))
      (node (ref "U1") (pin "F12") (pinfunction "GPIO38_F12") (pintype "bidirectional"))
    )
    (net (code "45") (name "AP4_USB0_N") (class "Default")
      (node (ref "U1") (pin "M8") (pinfunction "USB0PN_M8") (pintype "bidirectional"))
    )
    (net (code "46") (name "AP4_USB0_P") (class "Default")
      (node (ref "U1") (pin "M7") (pinfunction "USB0PP_M7") (pintype "bidirectional"))
    )
    (net (code "47") (name "AP4_VDDBH") (class "Default")
      (node (ref "C69") (pin "1") (pinfunction "1_1") (pintype "bidirectional"))
      (node (ref "L6") (pin "2") (pinfunction "2_2") (pintype "bidirectional"))
      (node (ref "RZ9") (pin "1") (pinfunction "1_1") (pintype "passive"))
      (node (ref "TP8") (pin "P$1") (pinfunction "TESTPOINT_P$1") (pintype "bidirectional"))
      (node (ref "U1") (pin "G12") (pinfunction "VDDBH--BLE_BUCK_VOUT_G12") (pintype "bidirectional"))
    )
    (net (code "48") (name "AP4_VDDBH_RF") (class "Default")
      (node (ref "C93") (pin "P$1") (pinfunction "1_P$1") (pintype "bidirectional"))
      (node (ref "RZ9") (pin "2") (pinfunction "2_2") (pintype "passive"))
      (node (ref "U1") (pin "J1") (pinfunction "VDDBH_RF--BLE_BUCK_RF_VOUT_J1") (pintype "bidirectional"))
    )
    (net (code "49") (name "AP4_VDDF") (class "Default")
      (node (ref "C61") (pin "P$1") (pinfunction "1_P$1") (pintype "bidirectional"))
      (node (ref "C75") (pin "P$1") (pinfunction "1_P$1") (pintype "bidirectional"))
      (node (ref "TP10") (pin "P$1") (pinfunction "TESTPOINT_P$1") (pintype "bidirectional"))
      (node (ref "U1") (pin "C2") (pinfunction "VDDF-MEM_C2") (pintype "bidirectional"))
    )
    (net (code "50") (name "AP4_VDDMIPI_1P8") (class "Default")
      (node (ref "C70") (pin "P$1") (pinfunction "1_P$1") (pintype "bidirectional"))
      (node (ref "RZ8") (pin "1") (pinfunction "1_1") (pintype "passive"))
      (node (ref "U1") (pin "H10") (pinfunction "VDD18-MIPI_H10") (pintype "bidirectional"))
    )
    (net (code "51") (name "AP4_VDDUSB_0P9") (class "Default")
      (node (ref "C73") (pin "P$1") (pinfunction "1_P$1") (pintype "bidirectional"))
      (node (ref "RZ6") (pin "1") (pinfunction "1_1") (pintype "passive"))
      (node (ref "U1") (pin "L7") (pinfunction "VDDUSB0P9_L7") (pintype "bidirectional"))
    )
    (net (code "52") (name "AP4_VDDUSB_3P3") (class "Default")
      (node (ref "C74") (pin "P$1") (pinfunction "1_P$1") (pintype "bidirectional"))
      (node (ref "RZ7") (pin "1") (pinfunction "1_1") (pintype "passive"))
      (node (ref "U1") (pin "K7") (pinfunction "VDDUSB33_K7") (pintype "bidirectional"))
    )
    (net (code "53") (name "AP4_~{RESET}") (class "Default")
      (node (ref "C76") (pin "1") (pinfunction "1_1") (pintype "passive"))
      (node (ref "D3") (pin "1") (pinfunction "C_1") (pintype "passive"))
      (node (ref "J1") (pin "3") (pinfunction "~{RESET}_3") (pintype "bidirectional"))
      (node (ref "J1") (pin "B3") (pinfunction "~{RESET}_B3") (pintype "bidirectional"))
      (node (ref "U1") (pin "A6") (pinfunction "~{RST}_A6") (pintype "input"))
    )
    (net (code "54") (name "BATT_THERM") (class "Default")
      (node (ref "J4") (pin "2") (pinfunction "2_2") (pintype "bidirectional"))
      (node (ref "J4") (pin "2SUPP") (pinfunction "2_2SUPP") (pintype "bidirectional"))
      (node (ref "JP2") (pin "3") (pinfunction "3_3") (pintype "passive"))
    )
    (net (code "55") (name "BATT_TS") (class "Default")
      (node (ref "JP2") (pin "2") (pinfunction "2_2") (pintype "passive"))
      (node (ref "U3") (pin "9") (pinfunction "TS_9") (pintype "bidirectional"))
    )
    (net (code "56") (name "BNO_ENV_SCL") (class "Default")
      (node (ref "R12") (pin "1") (pinfunction "1_1") (pintype "passive"))
      (node (ref "U6") (pin "15") (pinfunction "ENV_SCL_15") (pintype "bidirectional"))
    )
    (net (code "57") (name "BNO_ENV_SDA") (class "Default")
      (node (ref "R16") (pin "1") (pinfunction "1_1") (pintype "passive"))
      (node (ref "U6") (pin "16") (pinfunction "ENV_SDA_16") (pintype "bidirectional"))
    )
    (net (code "58") (name "D+") (class "Default")
      (node (ref "XJ1") (pin "A6") (pinfunction "DP1_A6") (pintype "bidirectional"))
      (node (ref "XJ1") (pin "B6") (pinfunction "DP2_B6") (pintype "bidirectional"))
    )
    (net (code "59") (name "D-") (class "Default")
      (node (ref "XJ1") (pin "A7") (pinfunction "DN1_A7") (pintype "bidirectional"))
      (node (ref "XJ1") (pin "B7") (pinfunction "DN2_B7") (pintype "bidirectional"))
    )
    (net (code "60") (name "DW_EXTON") (class "Default")
      (node (ref "JP12") (pin "2") (pinfunction "2_2") (pintype "passive"))
      (node (ref "RX1") (pin "2") (pinfunction "2_2") (pintype "passive"))
      (node (ref "S3") (pin "2") (pinfunction "CTL_2") (pintype "bidirectional"))
      (node (ref "S3") (pin "3") (pinfunction "CTL_3") (pintype "bidirectional"))
      (node (ref "VR3") (pin "3") (pinfunction "EN_3") (pintype "input"))
    )
    (net (code "61") (name "DW_EXTON_RAW") (class "Default")
      (node (ref "JP12") (pin "3") (pinfunction "3_3") (pintype "passive"))
      (node (ref "U2") (pin "A12") (pinfunction "EXTON_A12") (pintype "bidirectional"))
    )
    (net (code "62") (name "DW_GPIO6{slash}EXTRXE") (class "Default")
      (node (ref "JP3") (pin "3") (pinfunction "3_3") (pintype "passive"))
      (node (ref "TP6") (pin "P$1") (pinfunction "TESTPOINT_P$1") (pintype "bidirectional"))
      (node (ref "U2") (pin "C4") (pinfunction "GPIO6/EXTRXE/SPIPHA_C4") (pintype "bidirectional"))
    )
    (net (code "63") (name "DW_SYNC") (class "Default")
      (node (ref "TP7") (pin "P$1") (pinfunction "TESTPOINT_P$1") (pintype "bidirectional"))
      (node (ref "U2") (pin "G2") (pinfunction "GPIO7/SYNC_G2") (pintype "bidirectional"))
    )
    (net (code "64") (name "DW_VDD2_SUP") (class "Default")
      (node (ref "C13") (pin "P$1") (pinfunction "P$1_P$1") (pintype "bidirectional"))
      (node (ref "C24") (pin "P$1") (pinfunction "P$1_P$1") (pintype "bidirectional"))
      (node (ref "C55") (pin "P$1") (pinfunction "P$1_P$1") (pintype "bidirectional"))
      (node (ref "FB1") (pin "P$1") (pinfunction "P$1_P$1") (pintype "bidirectional"))
      (node (ref "RZ1") (pin "2") (pinfunction "2_2") (pintype "passive"))
      (node (ref "U2") (pin "B15") (pinfunction "VDD2B_B15") (pintype "bidirectional"))
    )
    (net (code "65") (name "DW_VDD3_SUP") (class "Default")
      (node (ref "C14") (pin "P$2") (pinfunction "P$2_P$2") (pintype "bidirectional"))
      (node (ref "C22") (pin "P$2") (pinfunction "P$2_P$2") (pintype "bidirectional"))
      (node (ref "C54") (pin "P$2") (pinfunction "P$2_P$2") (pintype "bidirectional"))
      (node (ref "RZ2") (pin "2") (pinfunction "2_2") (pintype "passive"))
      (node (ref "U2") (pin "D15") (pinfunction "VDD3_D15") (pintype "bidirectional"))
    )
    (net (code "66") (name "GND") (class "Default")
      (node (ref "C11") (pin "P$2") (pinfunction "P$2_P$2") (pintype "bidirectional"))
      (node (ref "C12") (pin "P$2") (pinfunction "P$2_P$2") (pintype "bidirectional"))
      (node (ref "C13") (pin "P$2") (pinfunction "P$2_P$2") (pintype "bidirectional"))
      (node (ref "C14") (pin "P$1") (pinfunction "P$1_P$1") (pintype "bidirectional"))
      (node (ref "C22") (pin "P$1") (pinfunction "P$1_P$1") (pintype "bidirectional"))
      (node (ref "C23") (pin "2") (pinfunction "2_2") (pintype "bidirectional"))
      (node (ref "C24") (pin "P$2") (pinfunction "P$2_P$2") (pintype "bidirectional"))
      (node (ref "C25") (pin "2") (pinfunction "2_2") (pintype "bidirectional"))
      (node (ref "C26") (pin "2") (pinfunction "2_2") (pintype "bidirectional"))
      (node (ref "C27") (pin "2") (pinfunction "2_2") (pintype "bidirectional"))
      (node (ref "C28") (pin "2") (pinfunction "2_2") (pintype "bidirectional"))
      (node (ref "C29") (pin "2") (pinfunction "2_2") (pintype "bidirectional"))
      (node (ref "C3") (pin "P$2") (pinfunction "P$2_P$2") (pintype "bidirectional"))
      (node (ref "C30") (pin "2") (pinfunction "2_2") (pintype "bidirectional"))
      (node (ref "C31") (pin "2") (pinfunction "2_2") (pintype "bidirectional"))
      (node (ref "C32") (pin "2") (pinfunction "2_2") (pintype "bidirectional"))
      (node (ref "C33") (pin "2") (pinfunction "2_2") (pintype "bidirectional"))
      (node (ref "C34") (pin "2") (pinfunction "2_2") (pintype "bidirectional"))
      (node (ref "C35") (pin "2") (pinfunction "2_2") (pintype "bidirectional"))
      (node (ref "C36") (pin "2") (pinfunction "2_2") (pintype "bidirectional"))
      (node (ref "C37") (pin "P$1") (pinfunction "P$1_P$1") (pintype "bidirectional"))
      (node (ref "C4") (pin "P$2") (pinfunction "P$2_P$2") (pintype "bidirectional"))
      (node (ref "C40") (pin "1") (pinfunction "1_1") (pintype "bidirectional"))
      (node (ref "C41") (pin "2") (pinfunction "2_2") (pintype "bidirectional"))
      (node (ref "C42") (pin "2") (pinfunction "2_2") (pintype "bidirectional"))
      (node (ref "C43") (pin "P$2") (pinfunction "P$2_P$2") (pintype "bidirectional"))
      (node (ref "C44") (pin "2") (pinfunction "2_2") (pintype "bidirectional"))
      (node (ref "C45") (pin "1") (pinfunction "1_1") (pintype "bidirectional"))
      (node (ref "C46") (pin "2") (pinfunction "2_2") (pintype "bidirectional"))
      (node (ref "C47") (pin "1") (pinfunction "1_1") (pintype "bidirectional"))
      (node (ref "C48") (pin "2") (pinfunction "2_2") (pintype "bidirectional"))
      (node (ref "C49") (pin "2") (pinfunction "2_2") (pintype "bidirectional"))
      (node (ref "C5") (pin "P$1") (pinfunction "1_P$1") (pintype "bidirectional"))
      (node (ref "C50") (pin "1") (pinfunction "1_1") (pintype "bidirectional"))
      (node (ref "C53") (pin "2") (pinfunction "2_2") (pintype "bidirectional"))
      (node (ref "C54") (pin "P$1") (pinfunction "P$1_P$1") (pintype "bidirectional"))
      (node (ref "C55") (pin "P$2") (pinfunction "P$2_P$2") (pintype "bidirectional"))
      (node (ref "C56") (pin "2") (pinfunction "2_2") (pintype "bidirectional"))
      (node (ref "C57") (pin "2") (pinfunction "2_2") (pintype "bidirectional"))
      (node (ref "C58") (pin "P$2") (pinfunction "2_P$2") (pintype "bidirectional"))
      (node (ref "C59") (pin "P$2") (pinfunction "2_P$2") (pintype "bidirectional"))
      (node (ref "C6") (pin "P$1") (pinfunction "1_P$1") (pintype "bidirectional"))
      (node (ref "C60") (pin "P$2") (pinfunction "2_P$2") (pintype "bidirectional"))
      (node (ref "C61") (pin "P$2") (pinfunction "2_P$2") (pintype "bidirectional"))
      (node (ref "C62") (pin "P$2") (pinfunction "2_P$2") (pintype "bidirectional"))
      (node (ref "C63") (pin "P$2") (pinfunction "2_P$2") (pintype "bidirectional"))
      (node (ref "C64") (pin "P$2") (pinfunction "2_P$2") (pintype "bidirectional"))
      (node (ref "C65") (pin "P$2") (pinfunction "2_P$2") (pintype "bidirectional"))
      (node (ref "C66") (pin "P$2") (pinfunction "2_P$2") (pintype "bidirectional"))
      (node (ref "C67") (pin "P$2") (pinfunction "2_P$2") (pintype "bidirectional"))
      (node (ref "C69") (pin "2") (pinfunction "2_2") (pintype "bidirectional"))
      (node (ref "C70") (pin "P$2") (pinfunction "2_P$2") (pintype "bidirectional"))
      (node (ref "C71") (pin "P$1") (pinfunction "1_P$1") (pintype "bidirectional"))
      (node (ref "C72") (pin "P$2") (pinfunction "2_P$2") (pintype "bidirectional"))
      (node (ref "C73") (pin "P$2") (pinfunction "2_P$2") (pintype "bidirectional"))
      (node (ref "C74") (pin "P$2") (pinfunction "2_P$2") (pintype "bidirectional"))
      (node (ref "C76") (pin "2") (pinfunction "2_2") (pintype "passive"))
      (node (ref "C77") (pin "P$2") (pinfunction "2_P$2") (pintype "bidirectional"))
      (node (ref "C78") (pin "P$2") (pinfunction "2_P$2") (pintype "bidirectional"))
      (node (ref "C79") (pin "P$1") (pinfunction "1_P$1") (pintype "bidirectional"))
      (node (ref "C80") (pin "2") (pinfunction "2_2") (pintype "passive"))
      (node (ref "C81") (pin "2") (pinfunction "2_2") (pintype "passive"))
      (node (ref "C90") (pin "P$2") (pinfunction "2_P$2") (pintype "bidirectional"))
      (node (ref "C91") (pin "P$2") (pinfunction "2_P$2") (pintype "bidirectional"))
      (node (ref "CX1") (pin "2") (pinfunction "2_2") (pintype "bidirectional"))
      (node (ref "CX2") (pin "2") (pinfunction "2_2") (pintype "bidirectional"))
      (node (ref "CX3") (pin "2") (pinfunction "2_2") (pintype "passive"))
      (node (ref "CX4") (pin "2") (pinfunction "2_2") (pintype "passive"))
      (node (ref "D3") (pin "2") (pinfunction "A_2") (pintype "passive"))
      (node (ref "J1") (pin "5") (pinfunction "GND_5") (pintype "bidirectional"))
      (node (ref "J1") (pin "B5") (pinfunction "GND_B5") (pintype "bidirectional"))
      (node (ref "J2") (pin "5") (pinfunction "GND_5") (pintype "bidirectional"))
      (node (ref "J2") (pin "B5") (pinfunction "GND_B5") (pintype "bidirectional"))
      (node (ref "J4") (pin "1") (pinfunction "1_1") (pintype "bidirectional"))
      (node (ref "J4") (pin "1SUPP") (pinfunction "1_1SUPP") (pintype "bidirectional"))
      (node (ref "JP3") (pin "1") (pinfunction "1_1") (pintype "passive"))
      (node (ref "JP9") (pin "2") (pinfunction "2_2") (pintype "passive"))
      (node (ref "Q2") (pin "S") (pinfunction "S_S") (pintype "passive"))
      (node (ref "R1") (pin "2") (pinfunction "2_2") (pintype "passive"))
      (node (ref "R15") (pin "1") (pinfunction "1_1") (pintype "passive"))
      (node (ref "R24") (pin "1") (pinfunction "1_1") (pintype "passive"))
      (node (ref "R25") (pin "2") (pinfunction "2_2") (pintype "passive"))
      (node (ref "R26") (pin "1") (pinfunction "1_1") (pintype "passive"))
      (node (ref "R27") (pin "1") (pinfunction "1_1") (pintype "passive"))
      (node (ref "R30") (pin "1") (pinfunction "1_1") (pintype "passive"))
      (node (ref "R6") (pin "2") (pinfunction "2_2") (pintype "passive"))
      (node (ref "RX14") (pin "1") (pinfunction "1_1") (pintype "passive"))
      (node (ref "RX7") (pin "1") (pinfunction "1_1") (pintype "passive"))
      (node (ref "RX9") (pin "1") (pinfunction "1_1") (pintype "passive"))
      (node (ref "RZ6") (pin "2") (pinfunction "2_2") (pintype "passive"))
      (node (ref "RZ7") (pin "2") (pinfunction "2_2") (pintype "passive"))
      (node (ref "RZ8") (pin "2") (pinfunction "2_2") (pintype "passive"))
      (node (ref "S2") (pin "10") (pinfunction "GND_10") (pintype "bidirectional"))
      (node (ref "S2") (pin "12") (pinfunction "GND_12") (pintype "bidirectional"))
      (node (ref "S2") (pin "2") (pinfunction "GND_2") (pintype "bidirectional"))
      (node (ref "S2") (pin "7") (pinfunction "GND_7") (pintype "bidirectional"))
      (node (ref "S2") (pin "8") (pinfunction "GND_8") (pintype "bidirectional"))
      (node (ref "S2") (pin "PAD") (pinfunction "GND_PAD") (pintype "bidirectional"))
      (node (ref "S3") (pin "6") (pinfunction "GND_6") (pintype "bidirectional"))
      (node (ref "S3") (pin "7") (pinfunction "GND_7") (pintype "bidirectional"))
      (node (ref "S3") (pin "PAD") (pinfunction "GND_PAD") (pintype "bidirectional"))
      (node (ref "S4") (pin "G1") (pinfunction "GND_G1") (pintype "bidirectional"))
      (node (ref "S4") (pin "G2") (pinfunction "GND_G2") (pintype "bidirectional"))
      (node (ref "U1") (pin "B12") (pinfunction "VSSAUDA_B12") (pintype "bidirectional"))
      (node (ref "U1") (pin "B2") (pinfunction "VSSP-BUCK_REGS_GND_B2") (pintype "bidirectional"))
      (node (ref "U1") (pin "B5") (pinfunction "VSSA-ANALOG_GND_B5") (pintype "bidirectional"))
      (node (ref "U1") (pin "D2") (pinfunction "VSS-DGND_FOR_VDDF_AND_PADS_D2") (pintype "bidirectional"))
      (node (ref "U1") (pin "E12") (pinfunction "VSSAUDD_E12") (pintype "bidirectional"))
      (node (ref "U1") (pin "H1") (pinfunction "VSSB-BLE_UNREG_GND_H1") (pintype "bidirectional"))
      (node (ref "U1") (pin "J10") (pinfunction "VSS18-MIPI_J10") (pintype "bidirectional"))
      (node (ref "U1") (pin "L1") (pinfunction "VSSVCO-BLECORE_GND_FOR_VCO_L1") (pintype "bidirectional"))
      (node (ref "U1") (pin "L2") (pinfunction "VSSS-HVSIMOBUCK_GND_L2") (pintype "bidirectional"))
      (node (ref "U1") (pin "L8") (pinfunction "VSSAUSB_L8") (pintype "bidirectional"))
      (node (ref "U2") (pin "A14") (pinfunction "VSS1_A14") (pintype "bidirectional"))
      (node (ref "U2") (pin "A2") (pinfunction "VSS_A2") (pintype "bidirectional"))
      (node (ref "U2") (pin "B11") (pinfunction "VSS1_B11") (pintype "bidirectional"))
      (node (ref "U2") (pin "B3") (pinfunction "VSS_B3") (pintype "bidirectional"))
      (node (ref "U2") (pin "C10") (pinfunction "VSS1_C10") (pintype "bidirectional"))
      (node (ref "U2") (pin "C12") (pinfunction "VSS3_C12") (pintype "bidirectional"))
      (node (ref "U2") (pin "C6") (pinfunction "VSS_C6") (pintype "bidirectional"))
      (node (ref "U2") (pin "C8") (pinfunction "VSS1_C8") (pintype "bidirectional"))
      (node (ref "U2") (pin "D11") (pinfunction "VSS2_D11") (pintype "bidirectional"))
      (node (ref "U2") (pin "D13") (pinfunction "VSS3_D13") (pintype "bidirectional"))
      (node (ref "U2") (pin "D5") (pinfunction "VSS_D5") (pintype "bidirectional"))
      (node (ref "U2") (pin "D7") (pinfunction "VSS_D7") (pintype "bidirectional"))
      (node (ref "U2") (pin "D9") (pinfunction "VSS1_D9") (pintype "bidirectional"))
      (node (ref "U2") (pin "E10") (pinfunction "GND-RF_E10") (pintype "bidirectional"))
      (node (ref "U2") (pin "E12") (pinfunction "GND-RF_E12") (pintype "bidirectional"))
      (node (ref "U2") (pin "E14") (pinfunction "VSS2_E14") (pintype "bidirectional"))
      (node (ref "U2") (pin "E6") (pinfunction "GND-RF_E6") (pintype "bidirectional"))
      (node (ref "U2") (pin "F7") (pinfunction "GND-RF_F7") (pintype "bidirectional"))
      (node (ref "U2") (pin "F9") (pinfunction "GND-RF_F9") (pintype "bidirectional"))
      (node (ref "U2") (pin "G10") (pinfunction "GND-RF_G10") (pintype "bidirectional"))
      (node (ref "U2") (pin "G6") (pinfunction "GND-RF_G6") (pintype "bidirectional"))
      (node (ref "U2") (pin "H1") (pinfunction "GND-RF_H1") (pintype "bidirectional"))
      (node (ref "U2") (pin "H13") (pinfunction "GND-RF_H13") (pintype "bidirectional"))
      (node (ref "U2") (pin "H3") (pinfunction "GND-RF_H3") (pintype "bidirectional"))
      (node (ref "U2") (pin "H7") (pinfunction "GND-RF_H7") (pintype "bidirectional"))
      (node (ref "U2") (pin "H9") (pinfunction "GND-RF_H9") (pintype "bidirectional"))
      (node (ref "U3") (pin "3") (pinfunction "VSS_3") (pintype "bidirectional"))
      (node (ref "U3") (pin "7") (pinfunction "ISET2_7") (pintype "bidirectional"))
      (node (ref "U3") (pin "PAD") (pinfunction "VSS_PAD") (pintype "bidirectional"))
      (node (ref "U4") (pin "1") (pinfunction "PGND_1") (pintype "bidirectional"))
      (node (ref "U4") (pin "10") (pinfunction "EN1_10") (pintype "bidirectional"))
      (node (ref "U4") (pin "11") (pinfunction "EN2_11") (pintype "bidirectional"))
      (node (ref "U4") (pin "20") (pinfunction "PGND_20") (pintype "bidirectional"))
      (node (ref "U4") (pin "PAD") (pinfunction "PGND_PAD") (pintype "bidirectional"))
      (node (ref "U6") (pin "10") (pinfunction "CLKSEL0_10") (pintype "output"))
      (node (ref "U6") (pin "2") (pinfunction "GND_2") (pintype "bidirectional"))
      (node (ref "U6") (pin "25") (pinfunction "GNDIO_25") (pintype "bidirectional"))
      (node (ref "U7") (pin "3") (pinfunction "GND_3") (pintype "bidirectional"))
      (node (ref "U7") (pin "4") (pinfunction "GND_4") (pintype "bidirectional"))
      (node (ref "U7") (pin "5") (pinfunction "GND_5") (pintype "bidirectional"))
      (node (ref "U7") (pin "7") (pinfunction "GND_7") (pintype "bidirectional"))
      (node (ref "U7") (pin "9") (pinfunction "GND_9") (pintype "bidirectional"))
      (node (ref "U8") (pin "4") (pinfunction "GND_4") (pintype "bidirectional"))
      (node (ref "VR1") (pin "13") (pinfunction "GND2_13") (pintype "bidirectional"))
      (node (ref "VR1") (pin "3") (pinfunction "GND2_3") (pintype "bidirectional"))
      (node (ref "VR1") (pin "9") (pinfunction "GND1_9") (pintype "bidirectional"))
      (node (ref "VR2") (pin "2") (pinfunction "GND_2") (pintype "bidirectional"))
      (node (ref "VR2") (pin "PAD") (pinfunction "GND_PAD") (pintype "bidirectional"))
      (node (ref "VR3") (pin "2") (pinfunction "GND_2") (pintype "bidirectional"))
      (node (ref "VR3") (pin "PAD") (pinfunction "GND_PAD") (pintype "bidirectional"))
      (node (ref "X1") (pin "2") (pinfunction "GND_2") (pintype "bidirectional"))
      (node (ref "X1") (pin "4") (pinfunction "GND_4") (pintype "bidirectional"))
      (node (ref "X4") (pin "2") (pinfunction "GND_2") (pintype "bidirectional"))
      (node (ref "X4") (pin "4") (pinfunction "GND_4") (pintype "bidirectional"))
      (node (ref "XJ1") (pin "A1/B12") (pinfunction "GND_A1/B12") (pintype "power_in"))
      (node (ref "XJ1") (pin "B1/A12") (pinfunction "GND_B1/A12") (pintype "power_in"))
      (node (ref "XJ1") (pin "S1") (pinfunction "GND_S1") (pintype "power_in"))
      (node (ref "XJ1") (pin "S2") (pinfunction "GND_S2") (pintype "power_in"))
      (node (ref "XJ1") (pin "S3") (pinfunction "GND_S3") (pintype "power_in"))
      (node (ref "XJ1") (pin "S4") (pinfunction "GND_S4") (pintype "power_in"))
      (node (ref "XR16") (pin "2") (pinfunction "2_2") (pintype "passive"))
      (node (ref "XR17") (pin "2") (pinfunction "2_2") (pintype "passive"))
      (node (ref "XR19") (pin "1") (pinfunction "1_1") (pintype "passive"))
    )
    (net (code "67") (name "Net-(A4-ANTENNA)") (class "Default")
      (node (ref "A4") (pin "S1") (pinfunction "ANTENNA_S1") (pintype "bidirectional"))
      (node (ref "L8") (pin "2") (pinfunction "2_2") (pintype "passive"))
    )
    (net (code "68") (name "Net-(C1-Pad1)") (class "Default")
      (node (ref "C1") (pin "1") (pinfunction "1_1") (pintype "passive"))
      (node (ref "L7") (pin "2") (pinfunction "2_2") (pintype "passive"))
      (node (ref "L8") (pin "1") (pinfunction "1_1") (pintype "passive"))
    )
    (net (code "69") (name "Net-(C2-1)") (class "Default")
      (node (ref "C2") (pin "P$1") (pinfunction "1_P$1") (pintype "bidirectional"))
      (node (ref "U2") (pin "H11") (pinfunction "RF1_H11") (pintype "bidirectional"))
    )
    (net (code "70") (name "Net-(C2-2)") (class "Default")
      (node (ref "C2") (pin "P$2") (pinfunction "2_P$2") (pintype "bidirectional"))
      (node (ref "S2") (pin "11") (pinfunction "RFC_11") (pintype "bidirectional"))
    )
    (net (code "71") (name "Net-(C5-2)") (class "Default")
      (node (ref "C5") (pin "P$2") (pinfunction "2_P$2") (pintype "bidirectional"))
      (node (ref "U6") (pin "27") (pinfunction "XIN32_27") (pintype "bidirectional"))
      (node (ref "X2") (pin "2") (pinfunction "2_2") (pintype "bidirectional"))
    )
    (net (code "72") (name "Net-(C6-2)") (class "Default")
      (node (ref "C6") (pin "P$2") (pinfunction "2_P$2") (pintype "bidirectional"))
      (node (ref "U6") (pin "26") (pinfunction "XOUT32/CLKSEL1_26") (pintype "bidirectional"))
      (node (ref "X2") (pin "1") (pinfunction "1_1") (pintype "bidirectional"))
    )
    (net (code "73") (name "Net-(C7-2)") (class "Default")
      (node (ref "C7") (pin "P$2") (pinfunction "2_P$2") (pintype "bidirectional"))
      (node (ref "R26") (pin "2") (pinfunction "2_2") (pintype "passive"))
      (node (ref "R28") (pin "1") (pinfunction "1_1") (pintype "passive"))
      (node (ref "VR1") (pin "10") (pinfunction "FB2_10") (pintype "bidirectional"))
    )
    (net (code "74") (name "Net-(C8-1)") (class "Default")
      (node (ref "C8") (pin "P$1") (pinfunction "1_P$1") (pintype "bidirectional"))
      (node (ref "R27") (pin "2") (pinfunction "2_2") (pintype "passive"))
      (node (ref "R29") (pin "2") (pinfunction "2_2") (pintype "passive"))
      (node (ref "VR1") (pin "4") (pinfunction "FB1_4") (pintype "bidirectional"))
    )
    (net (code "75") (name "Net-(C58-1)") (class "Default")
      (node (ref "C58") (pin "P$1") (pinfunction "1_P$1") (pintype "bidirectional"))
      (node (ref "U1") (pin "C1") (pinfunction "VDDS-SRAM_HV_SUP_C1") (pintype "bidirectional"))
    )
    (net (code "76") (name "Net-(C59-1)") (class "Default")
      (node (ref "C59") (pin "P$1") (pinfunction "1_P$1") (pintype "bidirectional"))
      (node (ref "U1") (pin "A3") (pinfunction "VDDC-CORE_A3") (pintype "bidirectional"))
    )
    (net (code "77") (name "Net-(C60-1)") (class "Default")
      (node (ref "C60") (pin "P$1") (pinfunction "1_P$1") (pintype "bidirectional"))
      (node (ref "U1") (pin "B3") (pinfunction "VDDC_LV-CORE_LV_B3") (pintype "bidirectional"))
    )
    (net (code "78") (name "Net-(C71-2)") (class "Default")
      (node (ref "C71") (pin "P$2") (pinfunction "2_P$2") (pintype "bidirectional"))
      (node (ref "U1") (pin "B10") (pinfunction "LPMICBIAS_B10") (pintype "output"))
    )
    (net (code "79") (name "Net-(C78-1)") (class "Default")
      (node (ref "C78") (pin "P$1") (pinfunction "1_P$1") (pintype "bidirectional"))
      (node (ref "RZ11") (pin "1") (pinfunction "1_1") (pintype "passive"))
      (node (ref "VR2") (pin "1") (pinfunction "OUT_1") (pintype "power_in"))
    )
    (net (code "80") (name "Net-(C79-2)") (class "Default")
      (node (ref "C79") (pin "P$2") (pinfunction "2_P$2") (pintype "bidirectional"))
      (node (ref "U1") (pin "A12") (pinfunction "LPADC_VREF_A12") (pintype "bidirectional"))
    )
    (net (code "81") (name "Net-(C91-1)") (class "Default")
      (node (ref "C91") (pin "P$1") (pinfunction "1_P$1") (pintype "bidirectional"))
      (node (ref "RZ4") (pin "1") (pinfunction "1_1") (pintype "passive"))
      (node (ref "VR3") (pin "1") (pinfunction "OUT_1") (pintype "power_in"))
    )
    (net (code "82") (name "Net-(D1-PadA1)") (class "Default")
      (node (ref "D1") (pin "A1") (pinfunction "A1_A1") (pintype "bidirectional"))
      (node (ref "D1") (pin "A2") (pinfunction "A2_A2") (pintype "bidirectional"))
      (node (ref "D2") (pin "A1") (pinfunction "A1_A1") (pintype "bidirectional"))
      (node (ref "D2") (pin "A2") (pinfunction "A2_A2") (pintype "bidirectional"))
      (node (ref "JP1") (pin "1") (pinfunction "1_1") (pintype "passive"))
    )
    (net (code "83") (name "Net-(D1-PadC1)") (class "Default")
      (node (ref "D1") (pin "C1") (pinfunction "C1_C1") (pintype "bidirectional"))
      (node (ref "R5") (pin "1") (pinfunction "1_1") (pintype "passive"))
    )
    (net (code "84") (name "Net-(D1-PadC2)") (class "Default")
      (node (ref "D1") (pin "C2") (pinfunction "C2_C2") (pintype "bidirectional"))
      (node (ref "R2") (pin "1") (pinfunction "1_1") (pintype "passive"))
    )
    (net (code "85") (name "Net-(D2-PadC1)") (class "Default")
      (node (ref "D2") (pin "C1") (pinfunction "C1_C1") (pintype "bidirectional"))
      (node (ref "R4") (pin "1") (pinfunction "1_1") (pintype "passive"))
    )
    (net (code "86") (name "Net-(D2-PadC2)") (class "Default")
      (node (ref "D2") (pin "C2") (pinfunction "C2_C2") (pintype "bidirectional"))
      (node (ref "R3") (pin "1") (pinfunction "1_1") (pintype "passive"))
    )
    (net (code "87") (name "Net-(JP2-Pad1)") (class "Default")
      (node (ref "JP2") (pin "1") (pinfunction "1_1") (pintype "passive"))
      (node (ref "XR19") (pin "2") (pinfunction "2_2") (pintype "passive"))
    )
    (net (code "88") (name "Net-(L1-1)") (class "Default")
      (node (ref "L1") (pin "P$1") (pinfunction "1_P$1") (pintype "bidirectional"))
      (node (ref "VR1") (pin "2") (pinfunction "LX2_2") (pintype "bidirectional"))
    )
    (net (code "89") (name "Net-(L2-2)") (class "Default")
      (node (ref "L2") (pin "P$2") (pinfunction "2_P$2") (pintype "bidirectional"))
      (node (ref "VR1") (pin "8") (pinfunction "LX1_8") (pintype "bidirectional"))
    )
    (net (code "90") (name "Net-(L4-1)") (class "Default")
      (node (ref "C17") (pin "2") (pinfunction "2_2") (pintype "bidirectional"))
      (node (ref "C18") (pin "2") (pinfunction "2_2") (pintype "bidirectional"))
      (node (ref "C19") (pin "2") (pinfunction "2_2") (pintype "bidirectional"))
      (node (ref "L4") (pin "P$1") (pinfunction "1_P$1") (pintype "bidirectional"))
    )
    (net (code "91") (name "Net-(L4-2)") (class "Default")
      (node (ref "C10") (pin "2") (pinfunction "2_2") (pintype "bidirectional"))
      (node (ref "C16") (pin "2") (pinfunction "2_2") (pintype "bidirectional"))
      (node (ref "C21") (pin "2") (pinfunction "2_2") (pintype "bidirectional"))
      (node (ref "C39") (pin "2") (pinfunction "2_2") (pintype "bidirectional"))
      (node (ref "C9") (pin "2") (pinfunction "2_2") (pintype "bidirectional"))
      (node (ref "L4") (pin "P$2") (pinfunction "2_P$2") (pintype "bidirectional"))
      (node (ref "U4") (pin "19") (pinfunction "AC2_19") (pintype "bidirectional"))
    )
    (net (code "92") (name "Net-(L5-1)") (class "Default")
      (node (ref "L5") (pin "P$1") (pinfunction "1_P$1") (pintype "bidirectional"))
      (node (ref "U1") (pin "A1") (pinfunction "SIMOBUCK_SW_A1") (pintype "bidirectional"))
    )
    (net (code "93") (name "Net-(L5-2)") (class "Default")
      (node (ref "L5") (pin "P$2") (pinfunction "2_P$2") (pintype "bidirectional"))
      (node (ref "U1") (pin "A2") (pinfunction "SIMOBUCK_SWSEL_A2") (pintype "bidirectional"))
    )
    (net (code "94") (name "Net-(LS1-N)") (class "Default")
      (node (ref "D4") (pin "ANODE") (pinfunction "ANODE_ANODE") (pintype "bidirectional"))
      (node (ref "LS1") (pin "-") (pinfunction "N_-") (pintype "passive"))
      (node (ref "Q2") (pin "D") (pinfunction "D_D") (pintype "passive"))
    )
    (net (code "95") (name "Net-(R6-Pad1)") (class "Default")
      (node (ref "R6") (pin "1") (pinfunction "1_1") (pintype "passive"))
      (node (ref "R7") (pin "2") (pinfunction "2_2") (pintype "passive"))
    )
    (net (code "96") (name "Net-(R8-Pad2)") (class "Default")
      (node (ref "R8") (pin "2") (pinfunction "2_2") (pintype "passive"))
      (node (ref "R9") (pin "1") (pinfunction "1_1") (pintype "passive"))
    )
    (net (code "97") (name "Net-(R13-Pad1)") (class "Default")
      (node (ref "R13") (pin "1") (pinfunction "1_1") (pintype "passive"))
      (node (ref "RX14") (pin "2") (pinfunction "2_2") (pintype "passive"))
    )
    (net (code "98") (name "Net-(R13-Pad2)") (class "Default")
      (node (ref "R13") (pin "2") (pinfunction "2_2") (pintype "passive"))
      (node (ref "RT1") (pin "1") (pinfunction "1_1") (pintype "passive"))
    )
    (net (code "99") (name "Net-(R18-Pad2)") (class "Default")
      (node (ref "R18") (pin "2") (pinfunction "2_2") (pintype "passive"))
      (node (ref "R23") (pin "1") (pinfunction "1_1") (pintype "passive"))
    )
    (net (code "100") (name "Net-(S3A-OUT)") (class "Default")
      (node (ref "C33") (pin "1") (pinfunction "1_1") (pintype "bidirectional"))
      (node (ref "RZ1") (pin "1") (pinfunction "1_1") (pintype "passive"))
      (node (ref "S3") (pin "8") (pinfunction "OUT_8") (pintype "bidirectional"))
    )
    (net (code "101") (name "Net-(S3B-OUT)") (class "Default")
      (node (ref "C25") (pin "1") (pinfunction "1_1") (pintype "bidirectional"))
      (node (ref "RZ2") (pin "1") (pinfunction "1_1") (pintype "passive"))
      (node (ref "S3") (pin "5") (pinfunction "OUT_5") (pintype "bidirectional"))
    )
    (net (code "102") (name "Net-(TP0-TESTPOINT)") (class "Default")
      (node (ref "TP0") (pin "P$1") (pinfunction "TESTPOINT_P$1") (pintype "bidirectional"))
      (node (ref "U2") (pin "C2") (pinfunction "GPIO0/RXOKLED_C2") (pintype "bidirectional"))
    )
    (net (code "103") (name "Net-(TP1-TESTPOINT)") (class "Default")
      (node (ref "TP1") (pin "P$1") (pinfunction "TESTPOINT_P$1") (pintype "bidirectional"))
      (node (ref "U2") (pin "D3") (pinfunction "GPIO1/SFDLED_D3") (pintype "bidirectional"))
    )
    (net (code "104") (name "Net-(TP2-TESTPOINT)") (class "Default")
      (node (ref "TP2") (pin "P$1") (pinfunction "TESTPOINT_P$1") (pintype "bidirectional"))
      (node (ref "U2") (pin "E4") (pinfunction "GPIO2/RXLED_E4") (pintype "bidirectional"))
    )
    (net (code "105") (name "Net-(TP3-TESTPOINT)") (class "Default")
      (node (ref "TP3") (pin "P$1") (pinfunction "TESTPOINT_P$1") (pintype "bidirectional"))
      (node (ref "U2") (pin "E2") (pinfunction "GPIO3/TXLED_E2") (pintype "bidirectional"))
    )
    (net (code "106") (name "Net-(TP4-TESTPOINT)") (class "Default")
      (node (ref "TP4") (pin "P$1") (pinfunction "TESTPOINT_P$1") (pintype "bidirectional"))
      (node (ref "U2") (pin "F1") (pinfunction "GPIO4/EXTPA_F1") (pintype "bidirectional"))
    )
    (net (code "107") (name "Net-(TP5-TESTPOINT)") (class "Default")
      (node (ref "TP5") (pin "P$1") (pinfunction "TESTPOINT_P$1") (pintype "bidirectional"))
      (node (ref "U2") (pin "D1") (pinfunction "GPIO5/EXTTXE/SPIPOL_D1") (pintype "bidirectional"))
    )
    (net (code "108") (name "Net-(U1-RFIOP)") (class "Default")
      (node (ref "CX5") (pin "1") (pinfunction "1_1") (pintype "passive"))
      (node (ref "L7") (pin "1") (pinfunction "1_1") (pintype "passive"))
      (node (ref "U1") (pin "M2") (pinfunction "RFIOP_M2") (pintype "bidirectional"))
    )
    (net (code "109") (name "Net-(U1-VDDBH_SW--BLE_BUCK_SW)") (class "Default")
      (node (ref "L6") (pin "1") (pinfunction "1_1") (pintype "bidirectional"))
      (node (ref "U1") (pin "H12") (pinfunction "VDDBH_SW--BLE_BUCK_SW_H12") (pintype "bidirectional"))
    )
    (net (code "110") (name "Net-(U1-XI)") (class "Default")
      (node (ref "C81") (pin "1") (pinfunction "1_1") (pintype "passive"))
      (node (ref "U1") (pin "A4") (pinfunction "XI_A4") (pintype "bidirectional"))
      (node (ref "X3") (pin "2") (pinfunction "2_2") (pintype "bidirectional"))
    )
    (net (code "111") (name "Net-(U1-XI32M)") (class "Default")
      (node (ref "CX4") (pin "1") (pinfunction "1_1") (pintype "passive"))
      (node (ref "U1") (pin "C12") (pinfunction "XI32M_C12") (pintype "bidirectional"))
      (node (ref "X1") (pin "3") (pinfunction "2_3") (pintype "bidirectional"))
    )
    (net (code "112") (name "Net-(U1-XO)") (class "Default")
      (node (ref "C80") (pin "1") (pinfunction "1_1") (pintype "passive"))
      (node (ref "U1") (pin "A5") (pinfunction "XO_A5") (pintype "bidirectional"))
      (node (ref "X3") (pin "1") (pinfunction "1_1") (pintype "bidirectional"))
    )
    (net (code "113") (name "Net-(U1-XO32M)") (class "Default")
      (node (ref "CX3") (pin "1") (pinfunction "1_1") (pintype "passive"))
      (node (ref "U1") (pin "D12") (pinfunction "XO32M_D12") (pintype "bidirectional"))
      (node (ref "X1") (pin "1") (pinfunction "1_1") (pintype "bidirectional"))
    )
    (net (code "114") (name "Net-(U2-RF2)") (class "Default")
      (node (ref "R1") (pin "1") (pinfunction "1_1") (pintype "passive"))
      (node (ref "U2") (pin "H5") (pinfunction "RF2_H5") (pintype "bidirectional"))
    )
    (net (code "115") (name "Net-(U2-VDD2A)") (class "Default")
      (node (ref "C12") (pin "P$1") (pinfunction "P$1_P$1") (pintype "bidirectional"))
      (node (ref "FB1") (pin "P$2") (pinfunction "P$2_P$2") (pintype "bidirectional"))
      (node (ref "U2") (pin "F15") (pinfunction "VDD2A_F15") (pintype "bidirectional"))
    )
    (net (code "116") (name "Net-(U2-VIO_D)") (class "Default")
      (node (ref "C23") (pin "1") (pinfunction "1_1") (pintype "bidirectional"))
      (node (ref "U2") (pin "A4") (pinfunction "VIO_D_A4") (pintype "bidirectional"))
    )
    (net (code "117") (name "Net-(U2-VTX_D)") (class "Default")
      (node (ref "C37") (pin "P$2") (pinfunction "P$2_P$2") (pintype "bidirectional"))
      (node (ref "U2") (pin "C14") (pinfunction "VTX_D_C14") (pintype "bidirectional"))
    )
    (net (code "118") (name "Net-(U2-XTI)") (class "Default")
      (node (ref "C3") (pin "P$1") (pinfunction "P$1_P$1") (pintype "bidirectional"))
      (node (ref "U2") (pin "H15") (pinfunction "XTI_H15") (pintype "bidirectional"))
      (node (ref "X4") (pin "1") (pinfunction "1_1") (pintype "bidirectional"))
    )
    (net (code "119") (name "Net-(U2-XTO)") (class "Default")
      (node (ref "C4") (pin "P$1") (pinfunction "P$1_P$1") (pintype "bidirectional"))
      (node (ref "U2") (pin "G14") (pinfunction "XTO_G14") (pintype "bidirectional"))
      (node (ref "X4") (pin "3") (pinfunction "2_3") (pintype "bidirectional"))
    )
    (net (code "120") (name "Net-(U3-ISET)") (class "Default")
      (node (ref "R15") (pin "2") (pinfunction "2_2") (pintype "passive"))
      (node (ref "U3") (pin "2") (pinfunction "ISET_2") (pintype "bidirectional"))
    )
    (net (code "121") (name "Net-(U3-PRETERM)") (class "Default")
      (node (ref "RX7") (pin "2") (pinfunction "2_2") (pintype "passive"))
      (node (ref "U3") (pin "4") (pinfunction "PRETERM_4") (pintype "bidirectional"))
    )
    (net (code "122") (name "Net-(U4-AC1)") (class "Default")
      (node (ref "C10") (pin "1") (pinfunction "1_1") (pintype "bidirectional"))
      (node (ref "C15") (pin "2") (pinfunction "2_2") (pintype "bidirectional"))
      (node (ref "C17") (pin "1") (pinfunction "1_1") (pintype "bidirectional"))
      (node (ref "C18") (pin "1") (pinfunction "1_1") (pintype "bidirectional"))
      (node (ref "C19") (pin "1") (pinfunction "1_1") (pintype "bidirectional"))
      (node (ref "C20") (pin "2") (pinfunction "2_2") (pintype "bidirectional"))
      (node (ref "C38") (pin "2") (pinfunction "2_2") (pintype "bidirectional"))
      (node (ref "C9") (pin "1") (pinfunction "1_1") (pintype "bidirectional"))
      (node (ref "U4") (pin "2") (pinfunction "AC1_2") (pintype "bidirectional"))
    )
    (net (code "123") (name "Net-(U4-BOOT1)") (class "Default")
      (node (ref "C15") (pin "1") (pinfunction "1_1") (pintype "bidirectional"))
      (node (ref "U4") (pin "3") (pinfunction "BOOT1_3") (pintype "bidirectional"))
    )
    (net (code "124") (name "Net-(U4-BOOT2)") (class "Default")
      (node (ref "C16") (pin "1") (pinfunction "1_1") (pintype "bidirectional"))
      (node (ref "U4") (pin "17") (pinfunction "BOOT2_17") (pintype "bidirectional"))
    )
    (net (code "125") (name "Net-(U4-CLAMP1)") (class "Default")
      (node (ref "C38") (pin "1") (pinfunction "1_1") (pintype "bidirectional"))
      (node (ref "U4") (pin "5") (pinfunction "CLAMP1_5") (pintype "bidirectional"))
    )
    (net (code "126") (name "Net-(U4-CLAMP2)") (class "Default")
      (node (ref "C39") (pin "1") (pinfunction "1_1") (pintype "bidirectional"))
      (node (ref "U4") (pin "16") (pinfunction "CLAMP2_16") (pintype "bidirectional"))
    )
    (net (code "127") (name "Net-(U4-COMM1)") (class "Default")
      (node (ref "C20") (pin "1") (pinfunction "1_1") (pintype "bidirectional"))
      (node (ref "U4") (pin "6") (pinfunction "COMM1_6") (pintype "bidirectional"))
    )
    (net (code "128") (name "Net-(U4-COMM2)") (class "Default")
      (node (ref "C21") (pin "1") (pinfunction "1_1") (pintype "bidirectional"))
      (node (ref "U4") (pin "15") (pinfunction "COMM2_15") (pintype "bidirectional"))
    )
    (net (code "129") (name "Net-(U4-FOD)") (class "Default")
      (node (ref "R23") (pin "2") (pinfunction "2_2") (pintype "passive"))
      (node (ref "R7") (pin "1") (pinfunction "1_1") (pintype "passive"))
      (node (ref "R9") (pin "2") (pinfunction "2_2") (pintype "passive"))
      (node (ref "U4") (pin "14") (pinfunction "FOD_14") (pintype "bidirectional"))
    )
    (net (code "130") (name "Net-(U4-ILIM)") (class "Default")
      (node (ref "R8") (pin "1") (pinfunction "1_1") (pintype "passive"))
      (node (ref "U4") (pin "12") (pinfunction "ILIM_12") (pintype "bidirectional"))
    )
    (net (code "131") (name "Net-(U4-RECT)") (class "Default")
      (node (ref "C28") (pin "1") (pinfunction "1_1") (pintype "bidirectional"))
      (node (ref "C56") (pin "1") (pinfunction "1_1") (pintype "bidirectional"))
      (node (ref "C57") (pin "1") (pinfunction "1_1") (pintype "bidirectional"))
      (node (ref "R18") (pin "1") (pinfunction "1_1") (pintype "passive"))
      (node (ref "U4") (pin "18") (pinfunction "RECT_18") (pintype "bidirectional"))
    )
    (net (code "132") (name "Net-(U6-CAP)") (class "Default")
      (node (ref "C36") (pin "1") (pinfunction "1_1") (pintype "bidirectional"))
      (node (ref "U6") (pin "9") (pinfunction "CAP_9") (pintype "bidirectional"))
    )
    (net (code "133") (name "Net-(U6-PS1)") (class "Default")
      (node (ref "RX9") (pin "2") (pinfunction "2_2") (pintype "passive"))
      (node (ref "RZ12") (pin "1") (pinfunction "1_1") (pintype "passive"))
      (node (ref "U6") (pin "5") (pinfunction "PS1_5") (pintype "input"))
    )
    (net (code "134") (name "Net-(U7-VCTRL)") (class "Default")
      (node (ref "JP3") (pin "2") (pinfunction "2_2") (pintype "passive"))
      (node (ref "U7") (pin "8") (pinfunction "VCTRL_8") (pintype "bidirectional"))
    )
    (net (code "135") (name "Net-(U7-VDD)") (class "Default")
      (node (ref "C11") (pin "P$1") (pinfunction "P$1_P$1") (pintype "bidirectional"))
      (node (ref "C43") (pin "P$1") (pinfunction "P$1_P$1") (pintype "bidirectional"))
      (node (ref "RZ4") (pin "2") (pinfunction "2_2") (pintype "passive"))
      (node (ref "U7") (pin "1") (pinfunction "VDD_1") (pintype "bidirectional"))
    )
    (net (code "136") (name "Net-(VR2-EN)") (class "Default")
      (node (ref "RZ10") (pin "2") (pinfunction "2_2") (pintype "passive"))
      (node (ref "VR2") (pin "3") (pinfunction "EN_3") (pintype "input"))
    )
    (net (code "137") (name "Net-(XJ1-CC1)") (class "Default")
      (node (ref "XJ1") (pin "A5") (pinfunction "CC1_A5") (pintype "bidirectional"))
      (node (ref "XR16") (pin "1") (pinfunction "1_1") (pintype "passive"))
    )
    (net (code "138") (name "Net-(XJ1-CC2)") (class "Default")
      (node (ref "XJ1") (pin "B5") (pinfunction "CC2_B5") (pintype "bidirectional"))
      (node (ref "XR17") (pin "1") (pinfunction "1_1") (pintype "passive"))
    )
    (net (code "139") (name "RF1") (class "Default")
      (node (ref "S2") (pin "9") (pinfunction "J2_9") (pintype "bidirectional"))
      (node (ref "U7") (pin "6") (pinfunction "LNA_OUT_6") (pintype "bidirectional"))
    )
    (net (code "140") (name "RF2") (class "Default")
      (node (ref "A2") (pin "FEED") (pinfunction "ANTENNA_FEED") (pintype "bidirectional"))
      (node (ref "S2") (pin "3") (pinfunction "J3_3") (pintype "bidirectional"))
    )
    (net (code "141") (name "RF3") (class "Default")
      (node (ref "A3") (pin "FEED") (pinfunction "ANTENNA_FEED") (pintype "bidirectional"))
      (node (ref "S2") (pin "1") (pinfunction "J1_1") (pintype "bidirectional"))
      (node (ref "S4") (pin "IN") (pinfunction "IN_IN") (pintype "bidirectional"))
      (node (ref "S4") (pin "OUT") (pinfunction "A_OUT") (pintype "bidirectional"))
    )
    (net (code "142") (name "VBAT") (class "Default")
      (node (ref "C42") (pin "1") (pinfunction "1_1") (pintype "bidirectional"))
      (node (ref "J4") (pin "3") (pinfunction "3_3") (pintype "bidirectional"))
      (node (ref "J4") (pin "3SUPP") (pinfunction "3_3SUPP") (pintype "bidirectional"))
      (node (ref "JP9") (pin "1") (pinfunction "1_1") (pintype "passive"))
      (node (ref "S1") (pin "2") (pinfunction "2_2") (pintype "passive"))
      (node (ref "U3") (pin "10") (pinfunction "OUT_10") (pintype "bidirectional"))
    )
    (net (code "143") (name "VBAT_SWITCHED") (class "Default")
      (node (ref "C45") (pin "2") (pinfunction "2_2") (pintype "bidirectional"))
      (node (ref "C48") (pin "1") (pinfunction "1_1") (pintype "bidirectional"))
      (node (ref "R31") (pin "2") (pinfunction "2_2") (pintype "passive"))
      (node (ref "R33") (pin "1") (pinfunction "1_1") (pintype "passive"))
      (node (ref "R34") (pin "1") (pinfunction "1_1") (pintype "passive"))
      (node (ref "S1") (pin "3") (pinfunction "3_3") (pintype "passive"))
      (node (ref "VR1") (pin "1") (pinfunction "VIN2_1") (pintype "bidirectional"))
      (node (ref "VR1") (pin "7") (pinfunction "VIN1_7") (pintype "bidirectional"))
    )
    (net (code "144") (name "VDDAUDA_1P8-CLEAN") (class "Default")
      (node (ref "C72") (pin "P$1") (pinfunction "1_P$1") (pintype "bidirectional"))
      (node (ref "RZ11") (pin "2") (pinfunction "2_2") (pintype "passive"))
      (node (ref "U1") (pin "B11") (pinfunction "VDDAUDA_B11") (pintype "bidirectional"))
    )
    (net (code "145") (name "VQI") (class "Default")
      (node (ref "C29") (pin "1") (pinfunction "1_1") (pintype "bidirectional"))
      (node (ref "C41") (pin "1") (pinfunction "1_1") (pintype "bidirectional"))
      (node (ref "C53") (pin "1") (pinfunction "1_1") (pintype "bidirectional"))
      (node (ref "Q1") (pin "A2") (pinfunction "D1_A2") (pintype "bidirectional"))
      (node (ref "Q1") (pin "A3") (pinfunction "D1_A3") (pintype "bidirectional"))
      (node (ref "Q1") (pin "B3") (pinfunction "D1_B3") (pintype "bidirectional"))
      (node (ref "U3") (pin "1") (pinfunction "IN_1") (pintype "bidirectional"))
      (node (ref "U4") (pin "4") (pinfunction "OUT_4") (pintype "bidirectional"))
    )
    (net (code "146") (name "VR1_1P8_EN") (class "Default")
      (node (ref "R34") (pin "2") (pinfunction "2_2") (pintype "passive"))
      (node (ref "VR1") (pin "6") (pinfunction "EN1_6") (pintype "bidirectional"))
    )
    (net (code "147") (name "VR1_2P5_EN") (class "Default")
      (node (ref "R33") (pin "2") (pinfunction "2_2") (pintype "passive"))
      (node (ref "VR1") (pin "12") (pinfunction "EN2_12") (pintype "bidirectional"))
    )
    (net (code "148") (name "VUSB") (class "Default")
      (node (ref "C40") (pin "2") (pinfunction "2_2") (pintype "bidirectional"))
      (node (ref "Q1") (pin "B2") (pinfunction "D2_B2") (pintype "bidirectional"))
      (node (ref "Q1") (pin "C2") (pinfunction "D2_C2") (pintype "bidirectional"))
      (node (ref "Q1") (pin "C3") (pinfunction "D2_C3") (pintype "bidirectional"))
      (node (ref "U4") (pin "9") (pinfunction "AD_9") (pintype "bidirectional"))
      (node (ref "XJ1") (pin "A4/B9") (pinfunction "VBUS_A4/B9") (pintype "power_in"))
      (node (ref "XJ1") (pin "B4/A9") (pinfunction "VBUS_B4/A9") (pintype "power_in"))
    )
    (net (code "149") (name "unconnected-(Q1-S-PadB1)") (class "Default")
      (node (ref "Q1") (pin "B1") (pinfunction "S_B1") (pintype "bidirectional"))
    )
    (net (code "150") (name "unconnected-(S1-Pad1)") (class "Default")
      (node (ref "S1") (pin "1") (pinfunction "1_1") (pintype "passive"))
    )
    (net (code "151") (name "unconnected-(U1-GPIO0-PadH3)") (class "Default")
      (node (ref "U1") (pin "H3") (pinfunction "GPIO0_H3") (pintype "bidirectional"))
    )
    (net (code "152") (name "unconnected-(U1-GPIO1-PadJ4)") (class "Default")
      (node (ref "U1") (pin "J4") (pinfunction "GPIO1_J4") (pintype "bidirectional"))
    )
    (net (code "153") (name "unconnected-(U1-GPIO2-PadK4)") (class "Default")
      (node (ref "U1") (pin "K4") (pinfunction "GPIO2_K4") (pintype "bidirectional"))
    )
    (net (code "154") (name "unconnected-(U1-GPIO4-PadM4)") (class "Default")
      (node (ref "U1") (pin "M4") (pinfunction "GPIO4_M4") (pintype "bidirectional"))
    )
    (net (code "155") (name "unconnected-(U1-GPIO5-PadH4)") (class "Default")
      (node (ref "U1") (pin "H4") (pinfunction "GPIO5_H4") (pintype "bidirectional"))
    )
    (net (code "156") (name "unconnected-(U1-GPIO7-PadJ6)") (class "Default")
      (node (ref "U1") (pin "J6") (pinfunction "GPIO7_J6") (pintype "bidirectional"))
    )
    (net (code "157") (name "unconnected-(U1-GPIO11-PadE4)") (class "Default")
      (node (ref "U1") (pin "E4") (pinfunction "GPIO11_E4") (pintype "bidirectional"))
    )
    (net (code "158") (name "unconnected-(U1-GPIO12-PadB4)") (class "Default")
      (node (ref "U1") (pin "B4") (pinfunction "GPIO12_B4") (pintype "bidirectional"))
    )
    (net (code "159") (name "unconnected-(U1-GPIO15-PadE5)") (class "Default")
      (node (ref "U1") (pin "E5") (pinfunction "GPIO15_E5") (pintype "bidirectional"))
    )
    (net (code "160") (name "unconnected-(U1-GPIO16-PadD7)") (class "Default")
      (node (ref "U1") (pin "D7") (pinfunction "GPIO16_D7") (pintype "bidirectional"))
    )
    (net (code "161") (name "unconnected-(U1-GPIO19-PadC3)") (class "Default")
      (node (ref "U1") (pin "C3") (pinfunction "GPIO19_C3") (pintype "bidirectional"))
    )
    (net (code "162") (name "unconnected-(U1-GPIO22-PadF3)") (class "Default")
      (node (ref "U1") (pin "F3") (pinfunction "GPIO22_F3") (pintype "bidirectional"))
    )
    (net (code "163") (name "unconnected-(U1-GPIO23-PadF2)") (class "Default")
      (node (ref "U1") (pin "F2") (pinfunction "GPIO23_F2") (pintype "bidirectional"))
    )
    (net (code "164") (name "unconnected-(U1-GPIO28-PadE3)") (class "Default")
      (node (ref "U1") (pin "E3") (pinfunction "GPIO28_E3") (pintype "bidirectional"))
    )
    (net (code "165") (name "unconnected-(U1-GPIO29-PadF4)") (class "Default")
      (node (ref "U1") (pin "F4") (pinfunction "GPIO29_F4") (pintype "bidirectional"))
    )
    (net (code "166") (name "unconnected-(U1-GPIO37-PadF11)") (class "Default")
      (node (ref "U1") (pin "F11") (pinfunction "GPIO37_F11") (pintype "bidirectional"))
    )
    (net (code "167") (name "unconnected-(U1-GPIO52-PadC10)") (class "Default")
      (node (ref "U1") (pin "C10") (pinfunction "GPIO52_C10") (pintype "bidirectional"))
    )
    (net (code "168") (name "unconnected-(U1-GPIO54-PadD10)") (class "Default")
      (node (ref "U1") (pin "D10") (pinfunction "GPIO54_D10") (pintype "bidirectional"))
    )
    (net (code "169") (name "unconnected-(U1-GPIO56-PadE10)") (class "Default")
      (node (ref "U1") (pin "E10") (pinfunction "GPIO56_E10") (pintype "bidirectional"))
    )
    (net (code "170") (name "unconnected-(U1-GPIO57-PadE9)") (class "Default")
      (node (ref "U1") (pin "E9") (pinfunction "GPIO57_E9") (pintype "bidirectional"))
    )
    (net (code "171") (name "unconnected-(U1-GPIO59-PadJ8)") (class "Default")
      (node (ref "U1") (pin "J8") (pinfunction "GPIO59_J8") (pintype "bidirectional"))
    )
    (net (code "172") (name "unconnected-(U1-GPIO61-PadK6)") (class "Default")
      (node (ref "U1") (pin "K6") (pinfunction "GPIO61_K6") (pintype "bidirectional"))
    )
    (net (code "173") (name "unconnected-(U1-GPIO62-PadL6)") (class "Default")
      (node (ref "U1") (pin "L6") (pinfunction "GPIO62_L6") (pintype "bidirectional"))
    )
    (net (code "174") (name "unconnected-(U1-GPIO64-PadB6)") (class "Default")
      (node (ref "U1") (pin "B6") (pinfunction "GPIO64_B6") (pintype "bidirectional"))
    )
    (net (code "175") (name "unconnected-(U1-GPIO67-PadC6)") (class "Default")
      (node (ref "U1") (pin "C6") (pinfunction "GPIO67_C6") (pintype "bidirectional"))
    )
    (net (code "176") (name "unconnected-(U1-GPIO68-PadB7)") (class "Default")
      (node (ref "U1") (pin "B7") (pinfunction "GPIO68_B7") (pintype "bidirectional"))
    )
    (net (code "177") (name "unconnected-(U1-GPIO70-PadC5)") (class "Default")
      (node (ref "U1") (pin "C5") (pinfunction "GPIO70_C5") (pintype "bidirectional"))
    )
    (net (code "178") (name "unconnected-(U1-GPIO71-PadC7)") (class "Default")
      (node (ref "U1") (pin "C7") (pinfunction "GPIO71_C7") (pintype "bidirectional"))
    )
    (net (code "179") (name "unconnected-(U1-GPIO73-PadD8)") (class "Default")
      (node (ref "U1") (pin "D8") (pinfunction "GPIO73_D8") (pintype "bidirectional"))
    )
    (net (code "180") (name "unconnected-(U1-GPIO74-PadG11)") (class "Default")
      (node (ref "U1") (pin "G11") (pinfunction "GPIO74_G11") (pintype "bidirectional"))
    )
    (net (code "181") (name "unconnected-(U1-GPIO75-PadH11)") (class "Default")
      (node (ref "U1") (pin "H11") (pinfunction "GPIO75_H11") (pintype "bidirectional"))
    )
    (net (code "182") (name "unconnected-(U1-GPIO76-PadJ11)") (class "Default")
      (node (ref "U1") (pin "J11") (pinfunction "GPIO76_J11") (pintype "bidirectional"))
    )
    (net (code "183") (name "unconnected-(U1-GPIO77-PadK11)") (class "Default")
      (node (ref "U1") (pin "K11") (pinfunction "GPIO77_K11") (pintype "bidirectional"))
    )
    (net (code "184") (name "unconnected-(U1-GPIO78-PadL11)") (class "Default")
      (node (ref "U1") (pin "L11") (pinfunction "GPIO78_L11") (pintype "bidirectional"))
    )
    (net (code "185") (name "unconnected-(U1-GPIO84-PadJ9)") (class "Default")
      (node (ref "U1") (pin "J9") (pinfunction "GPIO84_J9") (pintype "bidirectional"))
    )
    (net (code "186") (name "unconnected-(U1-GPIO85-PadH9)") (class "Default")
      (node (ref "U1") (pin "H9") (pinfunction "GPIO85_H9") (pintype "bidirectional"))
    )
    (net (code "187") (name "unconnected-(U1-GPIO86-PadG10)") (class "Default")
      (node (ref "U1") (pin "G10") (pinfunction "GPIO86_G10") (pintype "bidirectional"))
    )
    (net (code "188") (name "unconnected-(U1-GPIO87-PadG9)") (class "Default")
      (node (ref "U1") (pin "G9") (pinfunction "GPIO87_G9") (pintype "bidirectional"))
    )
    (net (code "189") (name "unconnected-(U1-GPIO89-PadF10)") (class "Default")
      (node (ref "U1") (pin "F10") (pinfunction "GPIO89_F10") (pintype "bidirectional"))
    )
    (net (code "190") (name "unconnected-(U1-GPIO90-PadJ2)") (class "Default")
      (node (ref "U1") (pin "J2") (pinfunction "GPIO90_J2") (pintype "bidirectional"))
    )
    (net (code "191") (name "unconnected-(U1-GPIO91-PadK2)") (class "Default")
      (node (ref "U1") (pin "K2") (pinfunction "GPIO91_K2") (pintype "bidirectional"))
    )
    (net (code "192") (name "unconnected-(U1-LPADC_D0NSE0-PadA10)") (class "Default")
      (node (ref "U1") (pin "A10") (pinfunction "LPADC_D0NSE0_A10") (pintype "input"))
    )
    (net (code "193") (name "unconnected-(U1-LPADC_D0PSE1-PadA11)") (class "Default")
      (node (ref "U1") (pin "A11") (pinfunction "LPADC_D0PSE1_A11") (pintype "input"))
    )
    (net (code "194") (name "unconnected-(U1-LPADC_D1NSE2-PadC11)") (class "Default")
      (node (ref "U1") (pin "C11") (pinfunction "LPADC_D1NSE2_C11") (pintype "input"))
    )
    (net (code "195") (name "unconnected-(U1-LPADC_D1PSE3-PadD11)") (class "Default")
      (node (ref "U1") (pin "D11") (pinfunction "LPADC_D1PSE3_D11") (pintype "input"))
    )
    (net (code "196") (name "unconnected-(U1-MIPI_CLKN-PadJ12)") (class "Default")
      (node (ref "U1") (pin "J12") (pinfunction "MIPI_CLKN_J12") (pintype "bidirectional"))
    )
    (net (code "197") (name "unconnected-(U1-MIPI_CLKP-PadK12)") (class "Default")
      (node (ref "U1") (pin "K12") (pinfunction "MIPI_CLKP_K12") (pintype "bidirectional"))
    )
    (net (code "198") (name "unconnected-(U1-MIPI_DON-PadL12)") (class "Default")
      (node (ref "U1") (pin "L12") (pinfunction "MIPI_DON_L12") (pintype "bidirectional"))
    )
    (net (code "199") (name "unconnected-(U1-MIPI_DOP-PadM12)") (class "Default")
      (node (ref "U1") (pin "M12") (pinfunction "MIPI_DOP_M12") (pintype "bidirectional"))
    )
    (net (code "200") (name "unconnected-(U1-TXEN-PadK1)") (class "Default")
      (node (ref "U1") (pin "K1") (pinfunction "TXEN_K1") (pintype "output"))
    )
    (net (code "201") (name "unconnected-(VR1-NC1-Pad5)") (class "Default")
      (node (ref "VR1") (pin "5") (pinfunction "NC1_5") (pintype "bidirectional"))
    )
    (net (code "202") (name "unconnected-(VR1-NC2-Pad11)") (class "Default")
      (node (ref "VR1") (pin "11") (pinfunction "NC2_11") (pintype "bidirectional"))
    )
    (net (code "203") (name "unconnected-(XJ1-SBU1-PadA8)") (class "Default")
      (node (ref "XJ1") (pin "A8") (pinfunction "SBU1_A8") (pintype "bidirectional"))
    )
    (net (code "204") (name "unconnected-(XJ1-SBU2-PadB8)") (class "Default")
      (node (ref "XJ1") (pin "B8") (pinfunction "SBU2_B8") (pintype "bidirectional"))
    )
    (net (code "205") (name "~{AD_EN}") (class "Default")
      (node (ref "Q1") (pin "A1") (pinfunction "G1_A1") (pintype "input"))
      (node (ref "Q1") (pin "C1") (pinfunction "G2_C1") (pintype "input"))
      (node (ref "U4") (pin "8") (pinfunction "~{AD-EN}_8") (pintype "bidirectional"))
    )
  )
)
